# schematic.net
KiCad netlist of a schematic drawn in Altium Designer
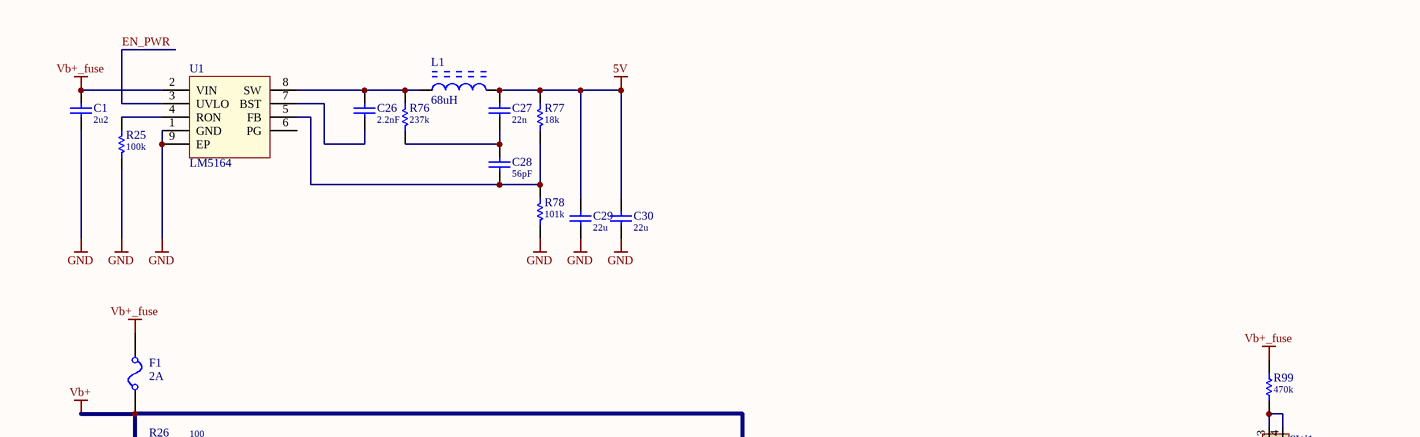
[diagram p0: schematic.SchDoc, top]
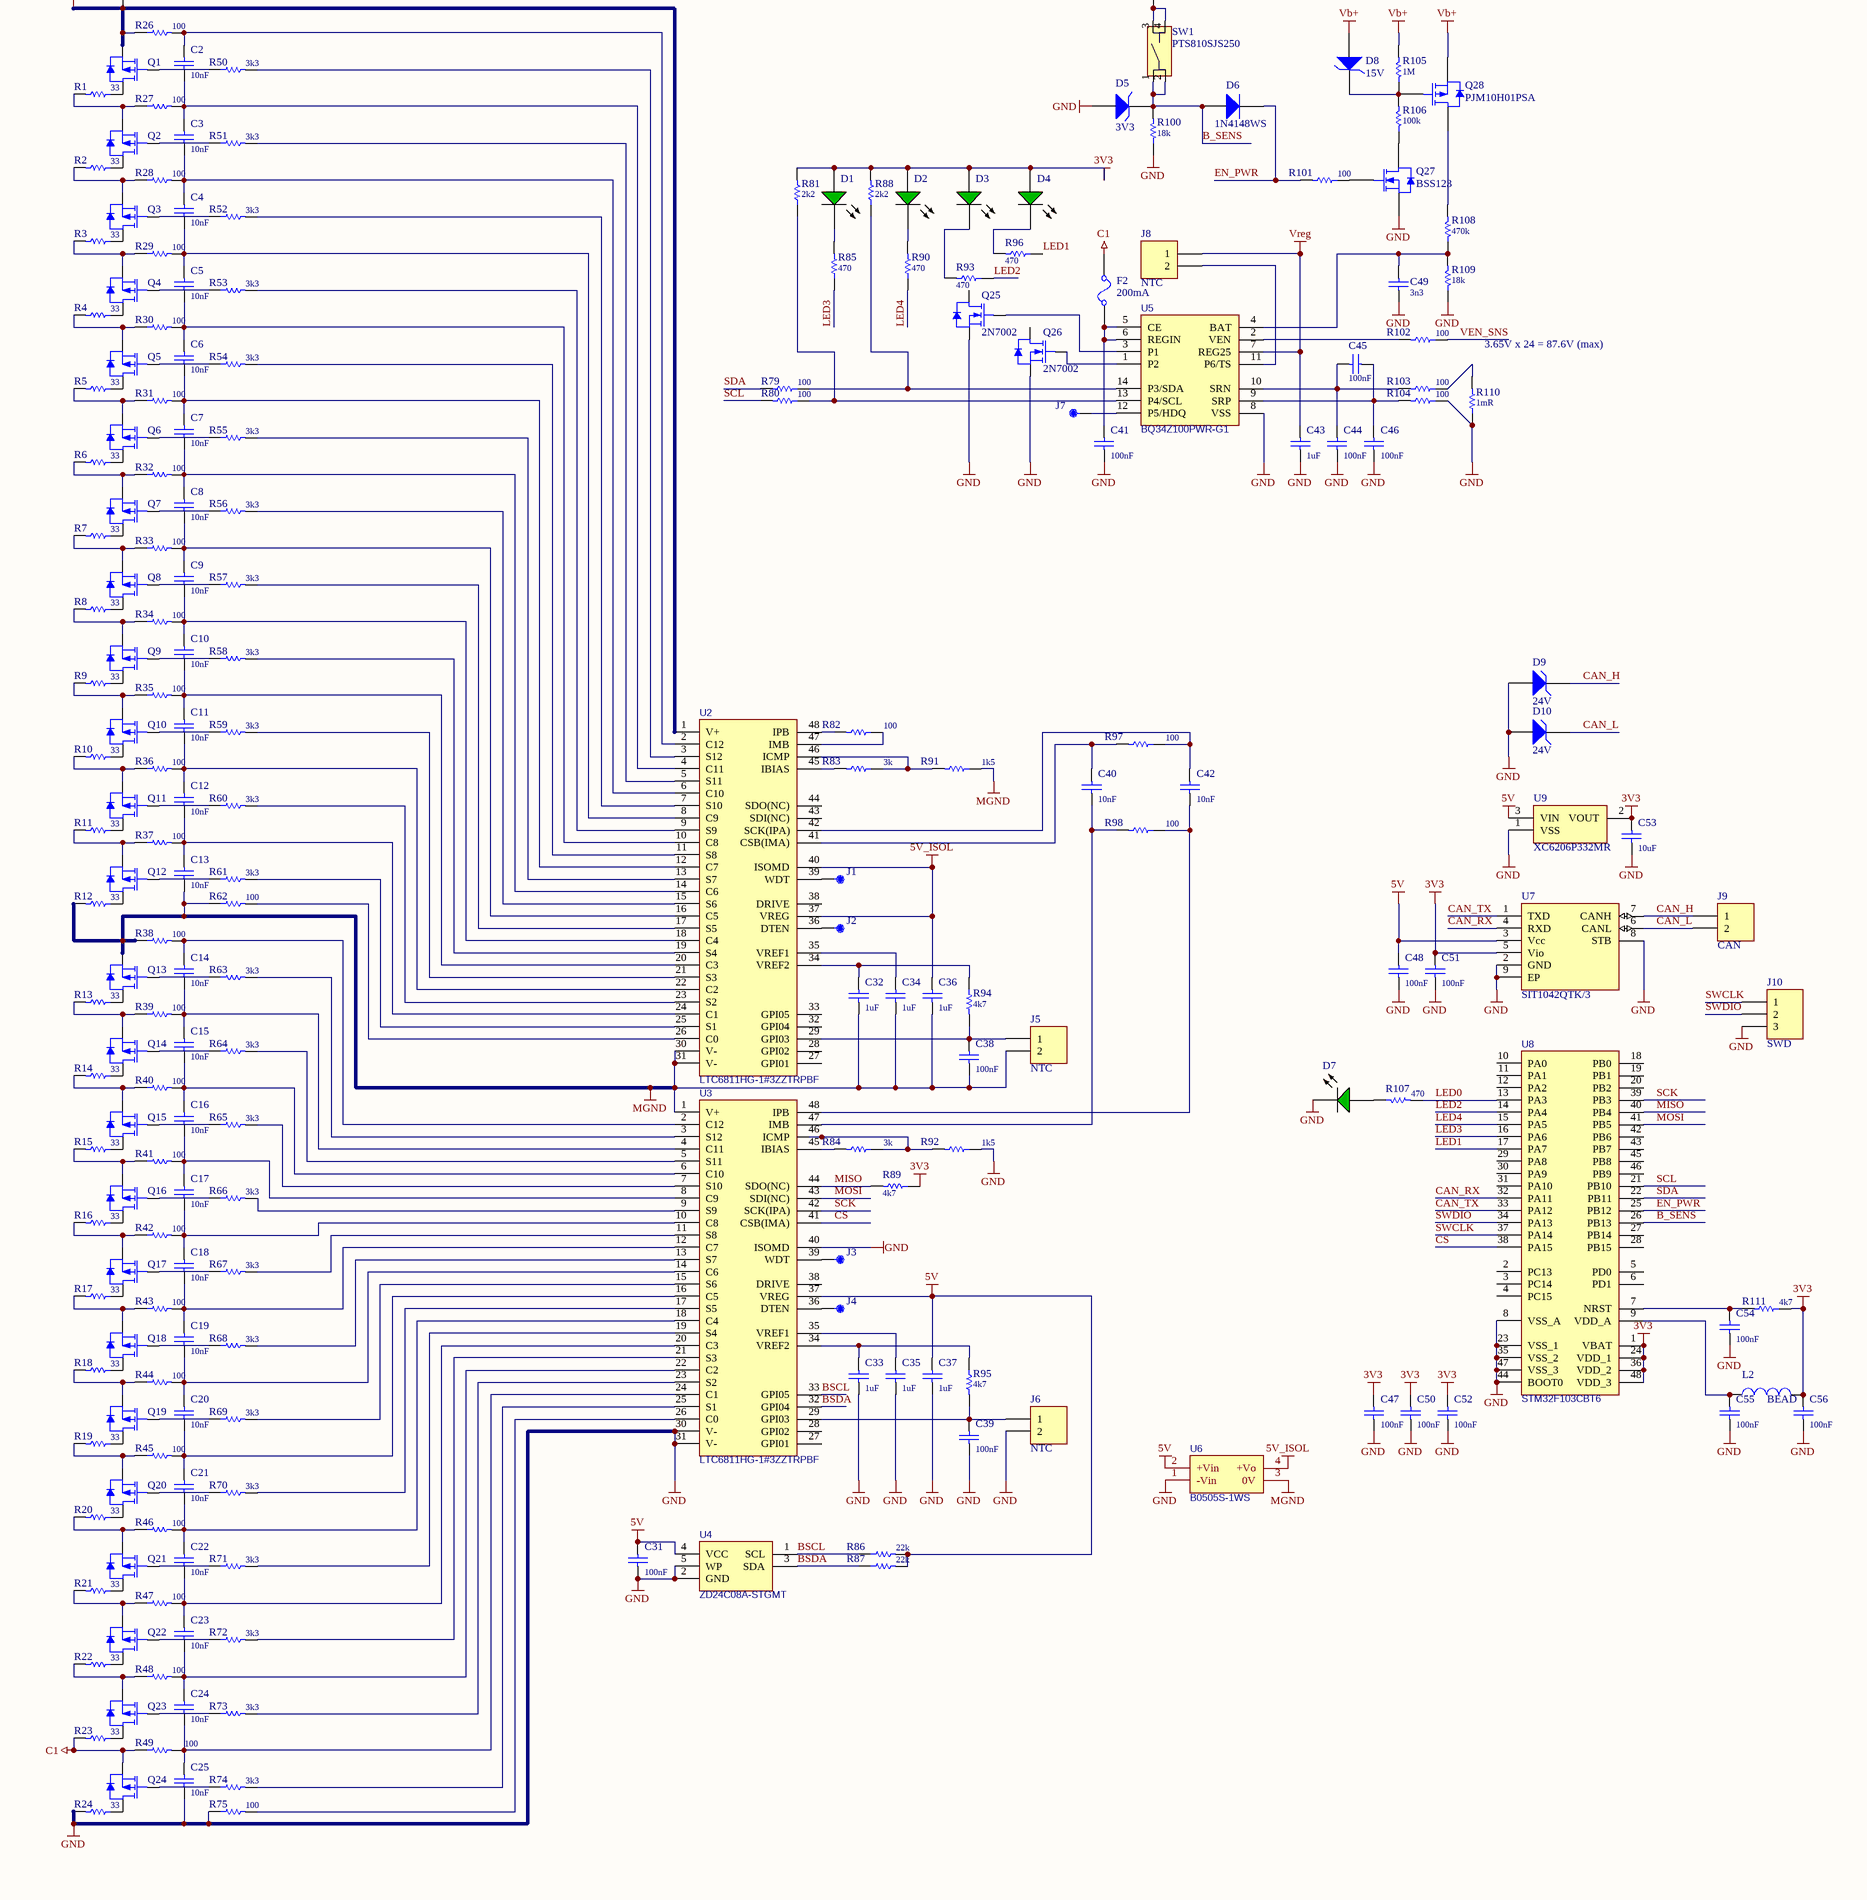
[diagram p1: schematic.SchDoc, bottom]

(export (version "E")
  (design (tool "Eeschema 10.0.6"))
  (components
    (comp (ref "C1")
      (value "2u2")
      (footprint "C1210")
      (description "2.2uF 100V 1210")
      (libsource (lib "Miscellaneous Devices") (part "CAP"))
    )
    (comp (ref "C2")
      (value "10nF")
      (footprint "C0603")
      (description "10nF 50V 0603")
      (libsource (lib "Miscellaneous Devices") (part "CAP"))
    )
    (comp (ref "C3")
      (value "10nF")
      (footprint "C0603")
      (description "10nF 50V 0603")
      (libsource (lib "Miscellaneous Devices") (part "CAP"))
    )
    (comp (ref "C4")
      (value "10nF")
      (footprint "C0603")
      (description "10nF 50V 0603")
      (libsource (lib "Miscellaneous Devices") (part "CAP"))
    )
    (comp (ref "C5")
      (value "10nF")
      (footprint "C0603")
      (description "10nF 50V 0603")
      (libsource (lib "Miscellaneous Devices") (part "CAP"))
    )
    (comp (ref "C6")
      (value "10nF")
      (footprint "C0603")
      (description "10nF 50V 0603")
      (libsource (lib "Miscellaneous Devices") (part "CAP"))
    )
    (comp (ref "C7")
      (value "10nF")
      (footprint "C0603")
      (description "10nF 50V 0603")
      (libsource (lib "Miscellaneous Devices") (part "CAP"))
    )
    (comp (ref "C8")
      (value "10nF")
      (footprint "C0603")
      (description "10nF 50V 0603")
      (libsource (lib "Miscellaneous Devices") (part "CAP"))
    )
    (comp (ref "C9")
      (value "10nF")
      (footprint "C0603")
      (description "10nF 50V 0603")
      (libsource (lib "Miscellaneous Devices") (part "CAP"))
    )
    (comp (ref "C10")
      (value "10nF")
      (footprint "C0603")
      (description "10nF 50V 0603")
      (libsource (lib "Miscellaneous Devices") (part "CAP"))
    )
    (comp (ref "C11")
      (value "10nF")
      (footprint "C0603")
      (description "10nF 50V 0603")
      (libsource (lib "Miscellaneous Devices") (part "CAP"))
    )
    (comp (ref "C12")
      (value "10nF")
      (footprint "C0603")
      (description "10nF 50V 0603")
      (libsource (lib "Miscellaneous Devices") (part "CAP"))
    )
    (comp (ref "C13")
      (value "10nF")
      (footprint "C0603")
      (description "10nF 50V 0603")
      (libsource (lib "Miscellaneous Devices") (part "CAP"))
    )
    (comp (ref "C14")
      (value "10nF")
      (footprint "C0603")
      (description "10nF 50V 0603")
      (libsource (lib "Miscellaneous Devices") (part "CAP"))
    )
    (comp (ref "C15")
      (value "10nF")
      (footprint "C0603")
      (description "10nF 50V 0603")
      (libsource (lib "Miscellaneous Devices") (part "CAP"))
    )
    (comp (ref "C16")
      (value "10nF")
      (footprint "C0603")
      (description "10nF 50V 0603")
      (libsource (lib "Miscellaneous Devices") (part "CAP"))
    )
    (comp (ref "C17")
      (value "10nF")
      (footprint "C0603")
      (description "10nF 50V 0603")
      (libsource (lib "Miscellaneous Devices") (part "CAP"))
    )
    (comp (ref "C18")
      (value "10nF")
      (footprint "C0603")
      (description "10nF 50V 0603")
      (libsource (lib "Miscellaneous Devices") (part "CAP"))
    )
    (comp (ref "C19")
      (value "10nF")
      (footprint "C0603")
      (description "10nF 50V 0603")
      (libsource (lib "Miscellaneous Devices") (part "CAP"))
    )
    (comp (ref "C20")
      (value "10nF")
      (footprint "C0603")
      (description "10nF 50V 0603")
      (libsource (lib "Miscellaneous Devices") (part "CAP"))
    )
    (comp (ref "C21")
      (value "10nF")
      (footprint "C0603")
      (description "10nF 50V 0603")
      (libsource (lib "Miscellaneous Devices") (part "CAP"))
    )
    (comp (ref "C22")
      (value "10nF")
      (footprint "C0603")
      (description "10nF 50V 0603")
      (libsource (lib "Miscellaneous Devices") (part "CAP"))
    )
    (comp (ref "C23")
      (value "10nF")
      (footprint "C0603")
      (description "10nF 50V 0603")
      (libsource (lib "Miscellaneous Devices") (part "CAP"))
    )
    (comp (ref "C24")
      (value "10nF")
      (footprint "C0603")
      (description "10nF 50V 0603")
      (libsource (lib "Miscellaneous Devices") (part "CAP"))
    )
    (comp (ref "C25")
      (value "10nF")
      (footprint "C0603")
      (description "10nF 50V 0603")
      (libsource (lib "Miscellaneous Devices") (part "CAP"))
    )
    (comp (ref "C26")
      (value "2.2nF")
      (footprint "C0603")
      (description "2.2nF 50V 0603")
      (libsource (lib "Miscellaneous Devices") (part "CAP"))
    )
    (comp (ref "C27")
      (value "22n")
      (footprint "C0603")
      (description "2.2nF 0603")
      (libsource (lib "Miscellaneous Devices") (part "CAP"))
    )
    (comp (ref "C28")
      (value "56pF")
      (footprint "C0603")
      (description "56pF 0603")
      (libsource (lib "Miscellaneous Devices") (part "CAP"))
    )
    (comp (ref "C29")
      (value "22u")
      (footprint "C1210")
      (description "22u 35V 1210")
      (libsource (lib "Miscellaneous Devices") (part "CAP"))
    )
    (comp (ref "C30")
      (value "22u")
      (footprint "C1210")
      (description "22u 35V 1210")
      (libsource (lib "Miscellaneous Devices") (part "CAP"))
    )
    (comp (ref "C31")
      (value "100nF")
      (footprint "C0402")
      (description "100nF 50V 0402")
      (libsource (lib "Miscellaneous Devices") (part "CAP"))
    )
    (comp (ref "C32")
      (value "1uF")
      (footprint "C0603")
      (description "1uF 0603")
      (libsource (lib "Miscellaneous Devices") (part "CAP"))
    )
    (comp (ref "C33")
      (value "1uF")
      (footprint "C0603")
      (description "1uF 0603")
      (libsource (lib "Miscellaneous Devices") (part "CAP"))
    )
    (comp (ref "C34")
      (value "1uF")
      (footprint "C0603")
      (description "1uF 0603")
      (libsource (lib "Miscellaneous Devices") (part "CAP"))
    )
    (comp (ref "C35")
      (value "1uF")
      (footprint "C0603")
      (description "1uF 0603")
      (libsource (lib "Miscellaneous Devices") (part "CAP"))
    )
    (comp (ref "C36")
      (value "1uF")
      (footprint "C0603")
      (description "1uF 0603")
      (libsource (lib "Miscellaneous Devices") (part "CAP"))
    )
    (comp (ref "C37")
      (value "1uF")
      (footprint "C0603")
      (description "1uF 0603")
      (libsource (lib "Miscellaneous Devices") (part "CAP"))
    )
    (comp (ref "C38")
      (value "100nF")
      (footprint "C0402")
      (description "100nF 50V 0402")
      (libsource (lib "Miscellaneous Devices") (part "CAP"))
    )
    (comp (ref "C39")
      (value "100nF")
      (footprint "C0402")
      (description "100nF 50V 0402")
      (libsource (lib "Miscellaneous Devices") (part "CAP"))
    )
    (comp (ref "C40")
      (value "10nF")
      (footprint "C0603")
      (description "10nF 50V 0402")
      (libsource (lib "Miscellaneous Devices") (part "CAP"))
    )
    (comp (ref "C41")
      (value "100nF")
      (footprint "C0603")
      (description "100nF 50V 0603")
      (libsource (lib "Miscellaneous Devices") (part "CAP"))
    )
    (comp (ref "C42")
      (value "10nF")
      (footprint "C0603")
      (description "10nF 50V 0402")
      (libsource (lib "Miscellaneous Devices") (part "CAP"))
    )
    (comp (ref "C43")
      (value "1uF")
      (footprint "C0603")
      (description "1uF 0603")
      (libsource (lib "Miscellaneous Devices") (part "CAP"))
    )
    (comp (ref "C44")
      (value "100nF")
      (footprint "C0603")
      (description "100nF 50V 0603")
      (libsource (lib "Miscellaneous Devices") (part "CAP"))
    )
    (comp (ref "C45")
      (value "100nF")
      (footprint "C0603")
      (description "100nF 50V 0603")
      (libsource (lib "Miscellaneous Devices") (part "CAP"))
    )
    (comp (ref "C46")
      (value "100nF")
      (footprint "C0603")
      (description "100nF 50V 0603")
      (libsource (lib "Miscellaneous Devices") (part "CAP"))
    )
    (comp (ref "C47")
      (value "100nF")
      (footprint "C0402")
      (description "100nF 50V 0402")
      (libsource (lib "Miscellaneous Devices") (part "CAP"))
    )
    (comp (ref "C48")
      (value "100nF")
      (footprint "C0402")
      (description "100nF 50V 0402")
      (libsource (lib "Miscellaneous Devices") (part "CAP"))
    )
    (comp (ref "C49")
      (value "3n3")
      (footprint "C0603")
      (description "3n3 100V 0603")
      (libsource (lib "Miscellaneous Devices") (part "CAP"))
    )
    (comp (ref "C50")
      (value "100nF")
      (footprint "C0402")
      (description "100nF 50V 0402")
      (libsource (lib "Miscellaneous Devices") (part "CAP"))
    )
    (comp (ref "C51")
      (value "100nF")
      (footprint "C0402")
      (description "100nF 50V 0402")
      (libsource (lib "Miscellaneous Devices") (part "CAP"))
    )
    (comp (ref "C52")
      (value "100nF")
      (footprint "C0402")
      (description "100nF 50V 0402")
      (libsource (lib "Miscellaneous Devices") (part "CAP"))
    )
    (comp (ref "C53")
      (value "10uF")
      (footprint "C1206")
      (description "10uf 50V 1206")
      (libsource (lib "Miscellaneous Devices") (part "CAP"))
    )
    (comp (ref "C54")
      (value "100nF")
      (footprint "C0402")
      (description "100nF 50V 0402")
      (libsource (lib "Miscellaneous Devices") (part "CAP"))
    )
    (comp (ref "C55")
      (value "100nF")
      (footprint "C0402")
      (description "100nF 50V 0402")
      (libsource (lib "Miscellaneous Devices") (part "CAP"))
    )
    (comp (ref "C56")
      (value "100nF")
      (footprint "C0402")
      (description "100nF 50V 0402")
      (libsource (lib "Miscellaneous Devices") (part "CAP"))
    )
    (comp (ref "D1")
      (value "GRN")
      (footprint "LED-0603-GRN")
      (description "LED 0603 GRN")
      (libsource (lib "Miscellaneous Devices") (part "LED-0603-GREEN"))
    )
    (comp (ref "D2")
      (value "GRN")
      (footprint "LED-0603-GRN")
      (description "LED 0603 GRN")
      (libsource (lib "Miscellaneous Devices") (part "LED-0603-GREEN"))
    )
    (comp (ref "D3")
      (value "GRN")
      (footprint "LED-0603-GRN")
      (description "LED 0603 GRN")
      (libsource (lib "Miscellaneous Devices") (part "LED-0603-GREEN"))
    )
    (comp (ref "D4")
      (value "GRN")
      (footprint "LED-0603-GRN")
      (description "LED 0603 GRN")
      (libsource (lib "Miscellaneous Devices") (part "LED-0603-GREEN"))
    )
    (comp (ref "D5")
      (value "3V3")
      (footprint "SOD-323")
      (libsource (lib "Miscellaneous Devices") (part "NCP51460SN33T1G"))
    )
    (comp (ref "D6")
      (value "1N4148WS")
      (footprint "SOD-323")
      (libsource (lib "Miscellaneous Devices") (part "US1M-13-F"))
    )
    (comp (ref "D7")
      (value "GRN")
      (footprint "LED-0603-GRN")
      (description "LED 0603 GRN")
      (libsource (lib "Miscellaneous Devices") (part "LED-0603-GREEN"))
    )
    (comp (ref "D8")
      (value "15V")
      (footprint "SOD-323")
      (description "BZT52C15S")
      (libsource (lib "") (part "NCP51460SN33T1G_1"))
    )
    (comp (ref "D9")
      (value "24V")
      (footprint "SOD-123FL")
      (description "P6SMB24A")
      (libsource (lib "Miscellaneous Devices") (part "SMCJ54A"))
    )
    (comp (ref "D10")
      (value "24V")
      (footprint "SOD-123FL")
      (description "P6SMB24A")
      (libsource (lib "Miscellaneous Devices") (part "SMCJ54A"))
    )
    (comp (ref "F1") (value "2A") (footprint "FUSE_2A_600V") (libsource (lib "Schlib1") (part "Component_1")))
    (comp (ref "F2") (value "200mA") (footprint "FUSE-1206") (libsource (lib "Schlib1") (part "Component_1")))
    (comp (ref "J1")
      (value "~")
      (footprint "TP30_SMD")
      (libsource (lib "Miscellaneous Connectors") (part "TP_Dup1"))
    )
    (comp (ref "J2")
      (value "~")
      (footprint "TP30_SMD")
      (libsource (lib "Miscellaneous Connectors") (part "TP_Dup1"))
    )
    (comp (ref "J3")
      (value "~")
      (footprint "TP30_SMD")
      (libsource (lib "Miscellaneous Connectors") (part "TP_Dup1"))
    )
    (comp (ref "J4")
      (value "~")
      (footprint "TP30_SMD")
      (libsource (lib "Miscellaneous Connectors") (part "TP_Dup1"))
    )
    (comp (ref "J5") (value "NTC") (footprint "HDR-1X2") (libsource (lib "Schlib1") (part "Header 2")))
    (comp (ref "J6") (value "NTC") (footprint "HDR-1X2") (libsource (lib "Schlib1") (part "Header 2")))
    (comp (ref "J7")
      (value "~")
      (footprint "TP30_SMD")
      (libsource (lib "Miscellaneous Connectors") (part "TP_Dup1"))
    )
    (comp (ref "J8") (value "NTC") (footprint "HDR-1X2") (libsource (lib "") (part "Header 2_1")))
    (comp (ref "J9") (value "CAN") (footprint "HDR-1X2") (libsource (lib "Schlib1") (part "Header 2")))
    (comp (ref "J10")
      (value "SWD")
      (footprint "HDR-1X3")
      (libsource (lib "Miscellaneous Devices") (part "Header 3"))
    )
    (comp (ref "L1")
      (value "68uH")
      (footprint "L0605-POWER")
      (description "PSPMAA0605H-680M-IGF")
      (libsource (lib "Miscellaneous Devices") (part "SRN3015-100M"))
    )
    (comp (ref "L2")
      (value "BEAD")
      (footprint "L0402")
      (description "BEAD 0402")
      (libsource (lib "Miscellaneous Devices") (part "BLM18AG601SN1D"))
    )
    (comp (ref "Q1")
      (value "BSS308PE-VB")
      (footprint "SOT-23")
      (libsource (lib "Miscellaneous Devices") (part "2N7002"))
    )
    (comp (ref "Q2")
      (value "BSS308PE-VB")
      (footprint "SOT-23")
      (libsource (lib "Miscellaneous Devices") (part "2N7002"))
    )
    (comp (ref "Q3")
      (value "BSS308PE-VB")
      (footprint "SOT-23")
      (libsource (lib "Miscellaneous Devices") (part "2N7002"))
    )
    (comp (ref "Q4")
      (value "BSS308PE-VB")
      (footprint "SOT-23")
      (libsource (lib "Miscellaneous Devices") (part "2N7002"))
    )
    (comp (ref "Q5")
      (value "BSS308PE-VB")
      (footprint "SOT-23")
      (libsource (lib "Miscellaneous Devices") (part "2N7002"))
    )
    (comp (ref "Q6")
      (value "BSS308PE-VB")
      (footprint "SOT-23")
      (libsource (lib "Miscellaneous Devices") (part "2N7002"))
    )
    (comp (ref "Q7")
      (value "BSS308PE-VB")
      (footprint "SOT-23")
      (libsource (lib "Miscellaneous Devices") (part "2N7002"))
    )
    (comp (ref "Q8")
      (value "BSS308PE-VB")
      (footprint "SOT-23")
      (libsource (lib "Miscellaneous Devices") (part "2N7002"))
    )
    (comp (ref "Q9")
      (value "BSS308PE-VB")
      (footprint "SOT-23")
      (libsource (lib "Miscellaneous Devices") (part "2N7002"))
    )
    (comp (ref "Q10")
      (value "BSS308PE-VB")
      (footprint "SOT-23")
      (libsource (lib "Miscellaneous Devices") (part "2N7002"))
    )
    (comp (ref "Q11")
      (value "BSS308PE-VB")
      (footprint "SOT-23")
      (libsource (lib "Miscellaneous Devices") (part "2N7002"))
    )
    (comp (ref "Q12")
      (value "BSS308PE-VB")
      (footprint "SOT-23")
      (libsource (lib "Miscellaneous Devices") (part "2N7002"))
    )
    (comp (ref "Q13")
      (value "BSS308PE-VB")
      (footprint "SOT-23")
      (libsource (lib "Miscellaneous Devices") (part "2N7002"))
    )
    (comp (ref "Q14")
      (value "BSS308PE-VB")
      (footprint "SOT-23")
      (libsource (lib "Miscellaneous Devices") (part "2N7002"))
    )
    (comp (ref "Q15")
      (value "BSS308PE-VB")
      (footprint "SOT-23")
      (libsource (lib "Miscellaneous Devices") (part "2N7002"))
    )
    (comp (ref "Q16")
      (value "BSS308PE-VB")
      (footprint "SOT-23")
      (libsource (lib "Miscellaneous Devices") (part "2N7002"))
    )
    (comp (ref "Q17")
      (value "BSS308PE-VB")
      (footprint "SOT-23")
      (libsource (lib "Miscellaneous Devices") (part "2N7002"))
    )
    (comp (ref "Q18")
      (value "BSS308PE-VB")
      (footprint "SOT-23")
      (libsource (lib "Miscellaneous Devices") (part "2N7002"))
    )
    (comp (ref "Q19")
      (value "BSS308PE-VB")
      (footprint "SOT-23")
      (libsource (lib "Miscellaneous Devices") (part "2N7002"))
    )
    (comp (ref "Q20")
      (value "BSS308PE-VB")
      (footprint "SOT-23")
      (libsource (lib "Miscellaneous Devices") (part "2N7002"))
    )
    (comp (ref "Q21")
      (value "BSS308PE-VB")
      (footprint "SOT-23")
      (libsource (lib "Miscellaneous Devices") (part "2N7002"))
    )
    (comp (ref "Q22")
      (value "BSS308PE-VB")
      (footprint "SOT-23")
      (libsource (lib "Miscellaneous Devices") (part "2N7002"))
    )
    (comp (ref "Q23")
      (value "BSS308PE-VB")
      (footprint "SOT-23")
      (libsource (lib "Miscellaneous Devices") (part "2N7002"))
    )
    (comp (ref "Q24")
      (value "BSS308PE-VB")
      (footprint "SOT-23")
      (libsource (lib "Miscellaneous Devices") (part "2N7002"))
    )
    (comp (ref "Q25") (value "2N7002") (footprint "SOT-23") (libsource (lib "") (part "2N7002_2")))
    (comp (ref "Q26") (value "2N7002") (footprint "SOT-23") (libsource (lib "") (part "2N7002_2")))
    (comp (ref "Q27") (value "BSS123") (footprint "SOT-23") (libsource (lib "") (part "2N7002_1")))
    (comp (ref "Q28") (value "PJM10H01PSA") (footprint "SOT-23") (libsource (lib "Schlib1") (part "2N7002")))
    (comp (ref "R1")
      (value "33")
      (footprint "R2512")
      (description "33R 2512")
      (libsource (lib "Miscellaneous Devices") (part "RES"))
    )
    (comp (ref "R2")
      (value "33")
      (footprint "R2512")
      (description "33R 2512")
      (libsource (lib "Miscellaneous Devices") (part "RES"))
    )
    (comp (ref "R3")
      (value "33")
      (footprint "R2512")
      (description "33R 2512")
      (libsource (lib "Miscellaneous Devices") (part "RES"))
    )
    (comp (ref "R4")
      (value "33")
      (footprint "R2512")
      (description "33R 2512")
      (libsource (lib "Miscellaneous Devices") (part "RES"))
    )
    (comp (ref "R5")
      (value "33")
      (footprint "R2512")
      (description "33R 2512")
      (libsource (lib "Miscellaneous Devices") (part "RES"))
    )
    (comp (ref "R6")
      (value "33")
      (footprint "R2512")
      (description "33R 2512")
      (libsource (lib "Miscellaneous Devices") (part "RES"))
    )
    (comp (ref "R7")
      (value "33")
      (footprint "R2512")
      (description "33R 2512")
      (libsource (lib "Miscellaneous Devices") (part "RES"))
    )
    (comp (ref "R8")
      (value "33")
      (footprint "R2512")
      (description "33R 2512")
      (libsource (lib "Miscellaneous Devices") (part "RES"))
    )
    (comp (ref "R9")
      (value "33")
      (footprint "R2512")
      (description "33R 2512")
      (libsource (lib "Miscellaneous Devices") (part "RES"))
    )
    (comp (ref "R10")
      (value "33")
      (footprint "R2512")
      (description "33R 2512")
      (libsource (lib "Miscellaneous Devices") (part "RES"))
    )
    (comp (ref "R11")
      (value "33")
      (footprint "R2512")
      (description "33R 2512")
      (libsource (lib "Miscellaneous Devices") (part "RES"))
    )
    (comp (ref "R12")
      (value "33")
      (footprint "R2512")
      (description "33R 2512")
      (libsource (lib "Miscellaneous Devices") (part "RES"))
    )
    (comp (ref "R13")
      (value "33")
      (footprint "R2512")
      (description "33R 2512")
      (libsource (lib "Miscellaneous Devices") (part "RES"))
    )
    (comp (ref "R14")
      (value "33")
      (footprint "R2512")
      (description "33R 2512")
      (libsource (lib "Miscellaneous Devices") (part "RES"))
    )
    (comp (ref "R15")
      (value "33")
      (footprint "R2512")
      (description "33R 2512")
      (libsource (lib "Miscellaneous Devices") (part "RES"))
    )
    (comp (ref "R16")
      (value "33")
      (footprint "R2512")
      (description "33R 2512")
      (libsource (lib "Miscellaneous Devices") (part "RES"))
    )
    (comp (ref "R17")
      (value "33")
      (footprint "R2512")
      (description "33R 2512")
      (libsource (lib "Miscellaneous Devices") (part "RES"))
    )
    (comp (ref "R18")
      (value "33")
      (footprint "R2512")
      (description "33R 2512")
      (libsource (lib "Miscellaneous Devices") (part "RES"))
    )
    (comp (ref "R19")
      (value "33")
      (footprint "R2512")
      (description "33R 2512")
      (libsource (lib "Miscellaneous Devices") (part "RES"))
    )
    (comp (ref "R20")
      (value "33")
      (footprint "R2512")
      (description "33R 2512")
      (libsource (lib "Miscellaneous Devices") (part "RES"))
    )
    (comp (ref "R21")
      (value "33")
      (footprint "R2512")
      (description "33R 2512")
      (libsource (lib "Miscellaneous Devices") (part "RES"))
    )
    (comp (ref "R22")
      (value "33")
      (footprint "R2512")
      (description "33R 2512")
      (libsource (lib "Miscellaneous Devices") (part "RES"))
    )
    (comp (ref "R23")
      (value "33")
      (footprint "R2512")
      (description "33R 2512")
      (libsource (lib "Miscellaneous Devices") (part "RES"))
    )
    (comp (ref "R24")
      (value "33")
      (footprint "R2512")
      (description "33R 2512")
      (libsource (lib "Miscellaneous Devices") (part "RES"))
    )
    (comp (ref "R25")
      (value "100k")
      (footprint "R0603")
      (description "100k 0603")
      (libsource (lib "Miscellaneous Devices") (part "RES"))
    )
    (comp (ref "R26")
      (value "100")
      (footprint "R0603")
      (description "100R 0603")
      (libsource (lib "Miscellaneous Devices") (part "RES"))
    )
    (comp (ref "R27")
      (value "100")
      (footprint "R0603")
      (description "100R 0603")
      (libsource (lib "Miscellaneous Devices") (part "RES"))
    )
    (comp (ref "R28")
      (value "100")
      (footprint "R0603")
      (description "100R 0603")
      (libsource (lib "Miscellaneous Devices") (part "RES"))
    )
    (comp (ref "R29")
      (value "100")
      (footprint "R0603")
      (description "100R 0603")
      (libsource (lib "Miscellaneous Devices") (part "RES"))
    )
    (comp (ref "R30")
      (value "100")
      (footprint "R0603")
      (description "100R 0603")
      (libsource (lib "Miscellaneous Devices") (part "RES"))
    )
    (comp (ref "R31")
      (value "100")
      (footprint "R0603")
      (description "100R 0603")
      (libsource (lib "Miscellaneous Devices") (part "RES"))
    )
    (comp (ref "R32")
      (value "100")
      (footprint "R0603")
      (description "100R 0603")
      (libsource (lib "Miscellaneous Devices") (part "RES"))
    )
    (comp (ref "R33")
      (value "100")
      (footprint "R0603")
      (description "100R 0603")
      (libsource (lib "Miscellaneous Devices") (part "RES"))
    )
    (comp (ref "R34")
      (value "100")
      (footprint "R0603")
      (description "100R 0603")
      (libsource (lib "Miscellaneous Devices") (part "RES"))
    )
    (comp (ref "R35")
      (value "100")
      (footprint "R0603")
      (description "100R 0603")
      (libsource (lib "Miscellaneous Devices") (part "RES"))
    )
    (comp (ref "R36")
      (value "100")
      (footprint "R0603")
      (description "100R 0603")
      (libsource (lib "Miscellaneous Devices") (part "RES"))
    )
    (comp (ref "R37")
      (value "100")
      (footprint "R0603")
      (description "100R 0603")
      (libsource (lib "Miscellaneous Devices") (part "RES"))
    )
    (comp (ref "R38")
      (value "100")
      (footprint "R0603")
      (description "100R 0603")
      (libsource (lib "Miscellaneous Devices") (part "RES"))
    )
    (comp (ref "R39")
      (value "100")
      (footprint "R0603")
      (description "100R 0603")
      (libsource (lib "Miscellaneous Devices") (part "RES"))
    )
    (comp (ref "R40")
      (value "100")
      (footprint "R0603")
      (description "100R 0603")
      (libsource (lib "Miscellaneous Devices") (part "RES"))
    )
    (comp (ref "R41")
      (value "100")
      (footprint "R0603")
      (description "100R 0603")
      (libsource (lib "Miscellaneous Devices") (part "RES"))
    )
    (comp (ref "R42")
      (value "100")
      (footprint "R0603")
      (description "100R 0603")
      (libsource (lib "Miscellaneous Devices") (part "RES"))
    )
    (comp (ref "R43")
      (value "100")
      (footprint "R0603")
      (description "100R 0603")
      (libsource (lib "Miscellaneous Devices") (part "RES"))
    )
    (comp (ref "R44")
      (value "100")
      (footprint "R0603")
      (description "100R 0603")
      (libsource (lib "Miscellaneous Devices") (part "RES"))
    )
    (comp (ref "R45")
      (value "100")
      (footprint "R0603")
      (description "100R 0603")
      (libsource (lib "Miscellaneous Devices") (part "RES"))
    )
    (comp (ref "R46")
      (value "100")
      (footprint "R0603")
      (description "100R 0603")
      (libsource (lib "Miscellaneous Devices") (part "RES"))
    )
    (comp (ref "R47")
      (value "100")
      (footprint "R0603")
      (description "100R 0603")
      (libsource (lib "Miscellaneous Devices") (part "RES"))
    )
    (comp (ref "R48")
      (value "100")
      (footprint "R0603")
      (description "100R 0603")
      (libsource (lib "Miscellaneous Devices") (part "RES"))
    )
    (comp (ref "R49")
      (value "100")
      (footprint "R0603")
      (description "100R 0603")
      (libsource (lib "Miscellaneous Devices") (part "RES"))
    )
    (comp (ref "R50")
      (value "3k3")
      (footprint "R0603")
      (description "3k3 0603")
      (libsource (lib "Miscellaneous Devices") (part "RES"))
    )
    (comp (ref "R51")
      (value "3k3")
      (footprint "R0603")
      (description "3k3 0603")
      (libsource (lib "Miscellaneous Devices") (part "RES"))
    )
    (comp (ref "R52")
      (value "3k3")
      (footprint "R0603")
      (description "3k3 0603")
      (libsource (lib "Miscellaneous Devices") (part "RES"))
    )
    (comp (ref "R53")
      (value "3k3")
      (footprint "R0603")
      (description "3k3 0603")
      (libsource (lib "Miscellaneous Devices") (part "RES"))
    )
    (comp (ref "R54")
      (value "3k3")
      (footprint "R0603")
      (description "3k3 0603")
      (libsource (lib "Miscellaneous Devices") (part "RES"))
    )
    (comp (ref "R55")
      (value "3k3")
      (footprint "R0603")
      (description "3k3 0603")
      (libsource (lib "Miscellaneous Devices") (part "RES"))
    )
    (comp (ref "R56")
      (value "3k3")
      (footprint "R0603")
      (description "3k3 0603")
      (libsource (lib "Miscellaneous Devices") (part "RES"))
    )
    (comp (ref "R57")
      (value "3k3")
      (footprint "R0603")
      (description "3k3 0603")
      (libsource (lib "Miscellaneous Devices") (part "RES"))
    )
    (comp (ref "R58")
      (value "3k3")
      (footprint "R0603")
      (description "3k3 0603")
      (libsource (lib "Miscellaneous Devices") (part "RES"))
    )
    (comp (ref "R59")
      (value "3k3")
      (footprint "R0603")
      (description "3k3 0603")
      (libsource (lib "Miscellaneous Devices") (part "RES"))
    )
    (comp (ref "R60")
      (value "3k3")
      (footprint "R0603")
      (description "3k3 0603")
      (libsource (lib "Miscellaneous Devices") (part "RES"))
    )
    (comp (ref "R61")
      (value "3k3")
      (footprint "R0603")
      (description "3k3 0603")
      (libsource (lib "Miscellaneous Devices") (part "RES"))
    )
    (comp (ref "R62")
      (value "100")
      (footprint "R0603")
      (description "100R 0603")
      (libsource (lib "Miscellaneous Devices") (part "RES"))
    )
    (comp (ref "R63")
      (value "3k3")
      (footprint "R0603")
      (description "3k3 0603")
      (libsource (lib "Miscellaneous Devices") (part "RES"))
    )
    (comp (ref "R64")
      (value "3k3")
      (footprint "R0603")
      (description "3k3 0603")
      (libsource (lib "Miscellaneous Devices") (part "RES"))
    )
    (comp (ref "R65")
      (value "3k3")
      (footprint "R0603")
      (description "3k3 0603")
      (libsource (lib "Miscellaneous Devices") (part "RES"))
    )
    (comp (ref "R66")
      (value "3k3")
      (footprint "R0603")
      (description "3k3 0603")
      (libsource (lib "Miscellaneous Devices") (part "RES"))
    )
    (comp (ref "R67")
      (value "3k3")
      (footprint "R0603")
      (description "3k3 0603")
      (libsource (lib "Miscellaneous Devices") (part "RES"))
    )
    (comp (ref "R68")
      (value "3k3")
      (footprint "R0603")
      (description "3k3 0603")
      (libsource (lib "Miscellaneous Devices") (part "RES"))
    )
    (comp (ref "R69")
      (value "3k3")
      (footprint "R0603")
      (description "3k3 0603")
      (libsource (lib "Miscellaneous Devices") (part "RES"))
    )
    (comp (ref "R70")
      (value "3k3")
      (footprint "R0603")
      (description "3k3 0603")
      (libsource (lib "Miscellaneous Devices") (part "RES"))
    )
    (comp (ref "R71")
      (value "3k3")
      (footprint "R0603")
      (description "3k3 0603")
      (libsource (lib "Miscellaneous Devices") (part "RES"))
    )
    (comp (ref "R72")
      (value "3k3")
      (footprint "R0603")
      (description "3k3 0603")
      (libsource (lib "Miscellaneous Devices") (part "RES"))
    )
    (comp (ref "R73")
      (value "3k3")
      (footprint "R0603")
      (description "3k3 0603")
      (libsource (lib "Miscellaneous Devices") (part "RES"))
    )
    (comp (ref "R74")
      (value "3k3")
      (footprint "R0603")
      (description "3k3 0603")
      (libsource (lib "Miscellaneous Devices") (part "RES"))
    )
    (comp (ref "R75")
      (value "100")
      (footprint "R0603")
      (description "100R 0603")
      (libsource (lib "Miscellaneous Devices") (part "RES"))
    )
    (comp (ref "R76")
      (value "237k")
      (footprint "R0603")
      (description "237k 0603")
      (libsource (lib "Miscellaneous Devices") (part "RES"))
    )
    (comp (ref "R77")
      (value "18k")
      (footprint "R0603")
      (description "18k 1% 0603")
      (libsource (lib "Miscellaneous Devices") (part "RES"))
    )
    (comp (ref "R78")
      (value "101k")
      (footprint "R0603")
      (description "101k 0603")
      (libsource (lib "Miscellaneous Devices") (part "RES"))
    )
    (comp (ref "R79")
      (value "100")
      (footprint "R0603")
      (description "100R 0603")
      (libsource (lib "Miscellaneous Devices") (part "RES"))
    )
    (comp (ref "R80")
      (value "100")
      (footprint "R0603")
      (description "100R 0603")
      (libsource (lib "Miscellaneous Devices") (part "RES"))
    )
    (comp (ref "R81")
      (value "2k2")
      (footprint "R0603")
      (description "2.2k 0603")
      (libsource (lib "Miscellaneous Devices") (part "RES"))
    )
    (comp (ref "R82")
      (value "100")
      (footprint "R0603")
      (description "100R 0603")
      (libsource (lib "Miscellaneous Devices") (part "RES"))
    )
    (comp (ref "R83")
      (value "3k")
      (footprint "R0603")
      (description "3k 0603")
      (libsource (lib "Miscellaneous Devices") (part "RES"))
    )
    (comp (ref "R84")
      (value "3k")
      (footprint "R0603")
      (description "3k 0603")
      (libsource (lib "Miscellaneous Devices") (part "RES"))
    )
    (comp (ref "R85")
      (value "470")
      (footprint "R0603")
      (description "470R 0603")
      (libsource (lib "Miscellaneous Devices") (part "RES"))
    )
    (comp (ref "R86")
      (value "22k")
      (footprint "R0402")
      (description "22k 0402")
      (libsource (lib "Miscellaneous Devices") (part "RES"))
    )
    (comp (ref "R87")
      (value "22k")
      (footprint "R0402")
      (description "22k 0402")
      (libsource (lib "Miscellaneous Devices") (part "RES"))
    )
    (comp (ref "R88")
      (value "2k2")
      (footprint "R0603")
      (description "2.2k 0603")
      (libsource (lib "Miscellaneous Devices") (part "RES"))
    )
    (comp (ref "R89")
      (value "4k7")
      (footprint "R0402")
      (description "4.7k 0603")
      (libsource (lib "Miscellaneous Devices") (part "RES"))
    )
    (comp (ref "R90")
      (value "470")
      (footprint "R0603")
      (description "470R 0603")
      (libsource (lib "Miscellaneous Devices") (part "RES"))
    )
    (comp (ref "R91")
      (value "1k5")
      (footprint "R0603")
      (description "1.5k 0603")
      (libsource (lib "Miscellaneous Devices") (part "RES"))
    )
    (comp (ref "R92")
      (value "1k5")
      (footprint "R0603")
      (description "1.5k 0603")
      (libsource (lib "Miscellaneous Devices") (part "RES"))
    )
    (comp (ref "R93")
      (value "470")
      (footprint "R0603")
      (description "470R 0603")
      (libsource (lib "Miscellaneous Devices") (part "RES"))
    )
    (comp (ref "R94")
      (value "4k7")
      (footprint "R0603")
      (description "4.7k 0603")
      (libsource (lib "Miscellaneous Devices") (part "RES"))
    )
    (comp (ref "R95")
      (value "4k7")
      (footprint "R0603")
      (description "4.7k 0603")
      (libsource (lib "Miscellaneous Devices") (part "RES"))
    )
    (comp (ref "R96")
      (value "470")
      (footprint "R0603")
      (description "470R 0603")
      (libsource (lib "Miscellaneous Devices") (part "RES"))
    )
    (comp (ref "R97")
      (value "100")
      (footprint "R0603")
      (description "100R 0603")
      (libsource (lib "Miscellaneous Devices") (part "RES"))
    )
    (comp (ref "R98")
      (value "100")
      (footprint "R0603")
      (description "100R 0603")
      (libsource (lib "Miscellaneous Devices") (part "RES"))
    )
    (comp (ref "R99")
      (value "470k")
      (footprint "R1206")
      (description "470k 1206")
      (libsource (lib "Miscellaneous Devices") (part "RES"))
    )
    (comp (ref "R100")
      (value "18k")
      (footprint "R0603")
      (description "18k 0603")
      (libsource (lib "Miscellaneous Devices") (part "RES"))
    )
    (comp (ref "R101")
      (value "100")
      (footprint "R0603")
      (description "100R 1% 0603")
      (libsource (lib "Miscellaneous Devices") (part "RES"))
    )
    (comp (ref "R102")
      (value "100")
      (footprint "R0603")
      (description "100R 0603")
      (libsource (lib "Miscellaneous Devices") (part "RES"))
    )
    (comp (ref "R103")
      (value "100")
      (footprint "R0603")
      (description "100R 0603")
      (libsource (lib "Miscellaneous Devices") (part "RES"))
    )
    (comp (ref "R104")
      (value "100")
      (footprint "R0603")
      (description "100R 0603")
      (libsource (lib "Miscellaneous Devices") (part "RES"))
    )
    (comp (ref "R105")
      (value "1M")
      (footprint "R1206")
      (description "1M 1206")
      (libsource (lib "Miscellaneous Devices") (part "RES"))
    )
    (comp (ref "R106")
      (value "100k")
      (footprint "R1206")
      (description "100k 1206")
      (libsource (lib "Miscellaneous Devices") (part "RES"))
    )
    (comp (ref "R107")
      (value "470")
      (footprint "R0603")
      (description "470 0603")
      (libsource (lib "Miscellaneous Devices") (part "RES"))
    )
    (comp (ref "R108")
      (value "470k")
      (footprint "R1206")
      (description "470k 1206")
      (libsource (lib "Miscellaneous Devices") (part "RES"))
    )
    (comp (ref "R109")
      (value "18k")
      (footprint "R0603")
      (description "18k 0603")
      (libsource (lib "Miscellaneous Devices") (part "RES"))
    )
    (comp (ref "R110")
      (value "1mR")
      (footprint "R5930_SHUNT")
      (description "HolRS5930-7W-1mR-1%")
      (libsource (lib "Miscellaneous Devices") (part "RES"))
    )
    (comp (ref "R111")
      (value "4k7")
      (footprint "R0402")
      (description "4k7 0402")
      (libsource (lib "Miscellaneous Devices") (part "RES"))
    )
    (comp (ref "SW1")
      (value "PTS810SJS250")
      (footprint "BTN_PTS810")
      (libsource (lib "Miscellaneous Devices") (part "Component_1"))
    )
    (comp (ref "U1") (value "LM5164") (footprint "PowerSOIC-8") (libsource (lib "Schlib2") (part "LM5164")))
    (comp (ref "U2")
      (value "LTC6811HG-1#3ZZTRPBF")
      (footprint "SSOP-48_L12.8-W5.3-P0.50-LS7.8-BL")
      (libsource (lib "Schlib1") (part "LTC6811HG-1#3ZZTRPBF"))
    )
    (comp (ref "U3")
      (value "LTC6811HG-1#3ZZTRPBF")
      (footprint "SSOP-48_L12.8-W5.3-P0.50-LS7.8-BL")
      (libsource (lib "Schlib1") (part "LTC6811HG-1#3ZZTRPBF"))
    )
    (comp (ref "U4")
      (value "ZD24C08A-STGMT")
      (footprint "SOT-23-5")
      (libsource (lib "Schlib1") (part "ZD24C08A-STGMT"))
    )
    (comp (ref "U5")
      (value "BQ34Z100PWR-G1")
      (footprint "TSSOP-14_L5.0-W4.4-P0.65-LS6.4-BL")
      (libsource (lib "Schlib1") (part "BQ34Z100PWR-G1"))
    )
    (comp (ref "U6")
      (value "B0505S-1WS")
      (footprint "B0505S-1WS")
      (libsource (lib "Schlib1") (part "B0505S-1WR3_C512048"))
    )
    (comp (ref "U7")
      (value "SIT1042QTK/3")
      (footprint "DFN8_3X3_P065")
      (description "IC INTERFACE CAN")
      (libsource (lib "Miscellaneous Devices") (part "LTC2875"))
    )
    (comp (ref "U8")
      (value "STM32F103CBT6")
      (footprint "LQFP-48")
      (libsource (lib "Schlib1") (part "STM32F103CBT6"))
    )
    (comp (ref "U9")
      (value "XC6206P332MR")
      (footprint "SOT-23")
      (libsource (lib "Schlib1") (part "Component_4_1"))
    )
  )
  (nets
    (net (code "1") (name "/BSCL") (class "Default")
      (node (ref "R86") (pin "1") (pinfunction "1_1") (pintype "passive"))
      (node (ref "U3") (pin "33") (pinfunction "GPI05_33") (pintype "passive"))
      (node (ref "U4") (pin "1") (pinfunction "SCL_1") (pintype "passive"))
    )
    (net (code "2") (name "/BSDA") (class "Default")
      (node (ref "R87") (pin "1") (pinfunction "1_1") (pintype "passive"))
      (node (ref "U3") (pin "32") (pinfunction "GPI04_32") (pintype "passive"))
      (node (ref "U4") (pin "3") (pinfunction "SDA_3") (pintype "passive"))
    )
    (net (code "3") (name "/B_SENS") (class "Default")
      (node (ref "D5") (pin "2") (pinfunction "-_2") (pintype "passive"))
      (node (ref "D6") (pin "1") (pinfunction "A_1") (pintype "passive"))
      (node (ref "R100") (pin "2") (pinfunction "2_2") (pintype "passive"))
      (node (ref "SW1") (pin "1") (pinfunction "1_1") (pintype "passive"))
      (node (ref "SW1") (pin "2") (pinfunction "2_2") (pintype "passive"))
      (node (ref "U8") (pin "26") (pinfunction "PB13_26") (pintype "passive"))
    )
    (net (code "4") (name "/CAN_H") (class "Default")
      (node (ref "D9") (pin "2") (pinfunction "K_2") (pintype "passive"))
      (node (ref "J9") (pin "1") (pinfunction "1_1") (pintype "passive"))
      (node (ref "U7") (pin "7") (pinfunction "CANH_7") (pintype "bidirectional"))
    )
    (net (code "5") (name "/CAN_L") (class "Default")
      (node (ref "D10") (pin "2") (pinfunction "K_2") (pintype "passive"))
      (node (ref "J9") (pin "2") (pinfunction "2_2") (pintype "passive"))
      (node (ref "U7") (pin "6") (pinfunction "CANL_6") (pintype "bidirectional"))
    )
    (net (code "6") (name "/CAN_RX") (class "Default")
      (node (ref "U7") (pin "4") (pinfunction "RXD_4") (pintype "passive"))
      (node (ref "U8") (pin "32") (pinfunction "PA11_32") (pintype "passive"))
    )
    (net (code "7") (name "/CAN_TX") (class "Default")
      (node (ref "U7") (pin "1") (pinfunction "TXD_1") (pintype "passive"))
      (node (ref "U8") (pin "33") (pinfunction "PA12_33") (pintype "passive"))
    )
    (net (code "8") (name "/CS") (class "Default")
      (node (ref "U3") (pin "41") (pinfunction "CSB(IMA)_41") (pintype "passive"))
      (node (ref "U8") (pin "38") (pinfunction "PA15_38") (pintype "passive"))
    )
    (net (code "9") (name "/EN_PWR") (class "Default")
      (node (ref "D6") (pin "2") (pinfunction "K_2") (pintype "passive"))
      (node (ref "R101") (pin "2") (pinfunction "2_2") (pintype "passive"))
      (node (ref "U1") (pin "3") (pinfunction "UVLO_3") (pintype "passive"))
      (node (ref "U8") (pin "25") (pinfunction "PB12_25") (pintype "passive"))
    )
    (net (code "10") (name "/LED0") (class "Default")
      (node (ref "R107") (pin "2") (pinfunction "2_2") (pintype "passive"))
      (node (ref "U8") (pin "13") (pinfunction "PA3_13") (pintype "passive"))
    )
    (net (code "11") (name "/LED1") (class "Default")
      (node (ref "R96") (pin "1") (pinfunction "1_1") (pintype "passive"))
      (node (ref "U8") (pin "17") (pinfunction "PA7_17") (pintype "passive"))
    )
    (net (code "12") (name "/LED2") (class "Default")
      (node (ref "R93") (pin "1") (pinfunction "1_1") (pintype "passive"))
      (node (ref "U8") (pin "14") (pinfunction "PA4_14") (pintype "passive"))
    )
    (net (code "13") (name "/LED3") (class "Default")
      (node (ref "R85") (pin "1") (pinfunction "1_1") (pintype "passive"))
      (node (ref "U8") (pin "16") (pinfunction "PA6_16") (pintype "passive"))
    )
    (net (code "14") (name "/LED4") (class "Default")
      (node (ref "R90") (pin "1") (pinfunction "1_1") (pintype "passive"))
      (node (ref "U8") (pin "15") (pinfunction "PA5_15") (pintype "passive"))
    )
    (net (code "15") (name "/MISO") (class "Default")
      (node (ref "R89") (pin "2") (pinfunction "2_2") (pintype "passive"))
      (node (ref "U3") (pin "44") (pinfunction "SDO(NC)_44") (pintype "passive"))
      (node (ref "U8") (pin "40") (pinfunction "PB4_40") (pintype "passive"))
    )
    (net (code "16") (name "/MOSI") (class "Default")
      (node (ref "U3") (pin "43") (pinfunction "SDI(NC)_43") (pintype "passive"))
      (node (ref "U8") (pin "41") (pinfunction "PB5_41") (pintype "passive"))
    )
    (net (code "17") (name "/SCK") (class "Default")
      (node (ref "U3") (pin "42") (pinfunction "SCK(IPA)_42") (pintype "passive"))
      (node (ref "U8") (pin "39") (pinfunction "PB3_39") (pintype "passive"))
    )
    (net (code "18") (name "/SCL") (class "Default")
      (node (ref "R80") (pin "2") (pinfunction "2_2") (pintype "passive"))
      (node (ref "U8") (pin "21") (pinfunction "PB10_21") (pintype "passive"))
    )
    (net (code "19") (name "/SDA") (class "Default")
      (node (ref "R79") (pin "2") (pinfunction "2_2") (pintype "passive"))
      (node (ref "U8") (pin "22") (pinfunction "PB11_22") (pintype "passive"))
    )
    (net (code "20") (name "/SWCLK") (class "Default")
      (node (ref "J10") (pin "1") (pinfunction "1_1") (pintype "passive"))
      (node (ref "U8") (pin "37") (pinfunction "PA14_37") (pintype "passive"))
    )
    (net (code "21") (name "/SWDIO") (class "Default")
      (node (ref "J10") (pin "2") (pinfunction "2_2") (pintype "passive"))
      (node (ref "U8") (pin "34") (pinfunction "PA13_34") (pintype "passive"))
    )
    (net (code "22") (name "/VEN_SNS") (class "Default")
      (node (ref "R102") (pin "1") (pinfunction "1_1") (pintype "passive"))
    )
    (net (code "23") (name "3V3") (class "Default")
      (node (ref "C47") (pin "2") (pinfunction "2_2") (pintype "passive"))
      (node (ref "C50") (pin "2") (pinfunction "2_2") (pintype "passive"))
      (node (ref "C51") (pin "2") (pinfunction "2_2") (pintype "passive"))
      (node (ref "C52") (pin "2") (pinfunction "2_2") (pintype "passive"))
      (node (ref "C53") (pin "2") (pinfunction "2_2") (pintype "passive"))
      (node (ref "C56") (pin "2") (pinfunction "2_2") (pintype "passive"))
      (node (ref "D1") (pin "1") (pinfunction "A_1") (pintype "passive"))
      (node (ref "D2") (pin "1") (pinfunction "A_1") (pintype "passive"))
      (node (ref "D3") (pin "1") (pinfunction "A_1") (pintype "passive"))
      (node (ref "D4") (pin "1") (pinfunction "A_1") (pintype "passive"))
      (node (ref "L2") (pin "1") (pinfunction "1_1") (pintype "passive"))
      (node (ref "R111") (pin "1") (pinfunction "1_1") (pintype "passive"))
      (node (ref "R81") (pin "2") (pinfunction "2_2") (pintype "passive"))
      (node (ref "R88") (pin "2") (pinfunction "2_2") (pintype "passive"))
      (node (ref "R89") (pin "1") (pinfunction "1_1") (pintype "passive"))
      (node (ref "U7") (pin "5") (pinfunction "Vio_5") (pintype "passive"))
      (node (ref "U8") (pin "1") (pinfunction "VBAT_1") (pintype "passive"))
      (node (ref "U8") (pin "24") (pinfunction "VDD_1_24") (pintype "passive"))
      (node (ref "U8") (pin "36") (pinfunction "VDD_2_36") (pintype "passive"))
      (node (ref "U8") (pin "48") (pinfunction "VDD_3_48") (pintype "passive"))
      (node (ref "U9") (pin "2") (pinfunction "VOUT_2") (pintype "passive"))
    )
    (net (code "24") (name "5V") (class "Default")
      (node (ref "C27") (pin "2") (pinfunction "2_2") (pintype "passive"))
      (node (ref "C29") (pin "2") (pinfunction "2_2") (pintype "passive"))
      (node (ref "C30") (pin "2") (pinfunction "2_2") (pintype "passive"))
      (node (ref "C31") (pin "2") (pinfunction "2_2") (pintype "passive"))
      (node (ref "C37") (pin "2") (pinfunction "2_2") (pintype "passive"))
      (node (ref "C48") (pin "2") (pinfunction "2_2") (pintype "passive"))
      (node (ref "L1") (pin "2") (pinfunction "2_2") (pintype "passive"))
      (node (ref "R77") (pin "1") (pinfunction "1_1") (pintype "passive"))
      (node (ref "R86") (pin "2") (pinfunction "2_2") (pintype "passive"))
      (node (ref "R87") (pin "2") (pinfunction "2_2") (pintype "passive"))
      (node (ref "U3") (pin "37") (pinfunction "VREG_37") (pintype "passive"))
      (node (ref "U4") (pin "4") (pinfunction "VCC_4") (pintype "passive"))
      (node (ref "U6") (pin "2") (pinfunction "+Vin_2") (pintype "passive"))
      (node (ref "U7") (pin "3") (pinfunction "Vcc_3") (pintype "passive"))
      (node (ref "U9") (pin "3") (pinfunction "VIN_3") (pintype "passive"))
    )
    (net (code "25") (name "5V_ISOL") (class "Default")
      (node (ref "C36") (pin "2") (pinfunction "2_2") (pintype "passive"))
      (node (ref "U2") (pin "37") (pinfunction "VREG_37") (pintype "passive"))
      (node (ref "U2") (pin "40") (pinfunction "ISOMD_40") (pintype "passive"))
      (node (ref "U6") (pin "4") (pinfunction "+Vo_4") (pintype "passive"))
    )
    (net (code "26") (name "C1") (class "Default")
      (node (ref "F2") (pin "2") (pinfunction "2_2") (pintype "passive"))
      (node (ref "Q24") (pin "2") (pinfunction "SOURCE_2") (pintype "passive"))
      (node (ref "R23") (pin "2") (pinfunction "2_2") (pintype "passive"))
      (node (ref "R49") (pin "1") (pinfunction "1_1") (pintype "passive"))
    )
    (net (code "27") (name "GND") (class "Default")
      (node (ref "C1") (pin "1") (pinfunction "1_1") (pintype "passive"))
      (node (ref "C25") (pin "1") (pinfunction "1_1") (pintype "passive"))
      (node (ref "C29") (pin "1") (pinfunction "1_1") (pintype "passive"))
      (node (ref "C30") (pin "1") (pinfunction "1_1") (pintype "passive"))
      (node (ref "C31") (pin "1") (pinfunction "1_1") (pintype "passive"))
      (node (ref "C33") (pin "1") (pinfunction "1_1") (pintype "passive"))
      (node (ref "C35") (pin "1") (pinfunction "1_1") (pintype "passive"))
      (node (ref "C37") (pin "1") (pinfunction "1_1") (pintype "passive"))
      (node (ref "C39") (pin "1") (pinfunction "1_1") (pintype "passive"))
      (node (ref "C41") (pin "1") (pinfunction "1_1") (pintype "passive"))
      (node (ref "C43") (pin "1") (pinfunction "1_1") (pintype "passive"))
      (node (ref "C44") (pin "1") (pinfunction "1_1") (pintype "passive"))
      (node (ref "C46") (pin "1") (pinfunction "1_1") (pintype "passive"))
      (node (ref "C47") (pin "1") (pinfunction "1_1") (pintype "passive"))
      (node (ref "C48") (pin "1") (pinfunction "1_1") (pintype "passive"))
      (node (ref "C49") (pin "2") (pinfunction "2_2") (pintype "passive"))
      (node (ref "C50") (pin "1") (pinfunction "1_1") (pintype "passive"))
      (node (ref "C51") (pin "1") (pinfunction "1_1") (pintype "passive"))
      (node (ref "C52") (pin "1") (pinfunction "1_1") (pintype "passive"))
      (node (ref "C53") (pin "1") (pinfunction "1_1") (pintype "passive"))
      (node (ref "C54") (pin "1") (pinfunction "1_1") (pintype "passive"))
      (node (ref "C55") (pin "1") (pinfunction "1_1") (pintype "passive"))
      (node (ref "C56") (pin "1") (pinfunction "1_1") (pintype "passive"))
      (node (ref "D10") (pin "1") (pinfunction "A_1") (pintype "passive"))
      (node (ref "D5") (pin "1") (pinfunction "+_1") (pintype "passive"))
      (node (ref "D7") (pin "2") (pinfunction "K_2") (pintype "passive"))
      (node (ref "D9") (pin "1") (pinfunction "A_1") (pintype "passive"))
      (node (ref "J10") (pin "3") (pinfunction "3_3") (pintype "passive"))
      (node (ref "J6") (pin "2") (pinfunction "2_2") (pintype "passive"))
      (node (ref "Q25") (pin "2") (pinfunction "SOURCE_2") (pintype "passive"))
      (node (ref "Q26") (pin "2") (pinfunction "SOURCE_2") (pintype "passive"))
      (node (ref "Q27") (pin "2") (pinfunction "SOURCE_2") (pintype "passive"))
      (node (ref "R100") (pin "1") (pinfunction "1_1") (pintype "passive"))
      (node (ref "R104") (pin "1") (pinfunction "1_1") (pintype "passive"))
      (node (ref "R109") (pin "1") (pinfunction "1_1") (pintype "passive"))
      (node (ref "R110") (pin "1") (pinfunction "1_1") (pintype "passive"))
      (node (ref "R24") (pin "2") (pinfunction "2_2") (pintype "passive"))
      (node (ref "R25") (pin "2") (pinfunction "2_2") (pintype "passive"))
      (node (ref "R75") (pin "1") (pinfunction "1_1") (pintype "passive"))
      (node (ref "R78") (pin "2") (pinfunction "2_2") (pintype "passive"))
      (node (ref "R92") (pin "1") (pinfunction "1_1") (pintype "passive"))
      (node (ref "U1") (pin "1") (pinfunction "GND_1") (pintype "power_in"))
      (node (ref "U1") (pin "9") (pinfunction "EP_9") (pintype "passive"))
      (node (ref "U3") (pin "30") (pinfunction "V-_30") (pintype "passive"))
      (node (ref "U3") (pin "31") (pinfunction "V-_31") (pintype "passive"))
      (node (ref "U3") (pin "40") (pinfunction "ISOMD_40") (pintype "passive"))
      (node (ref "U4") (pin "2") (pinfunction "GND_2") (pintype "passive"))
      (node (ref "U4") (pin "5") (pinfunction "WP_5") (pintype "passive"))
      (node (ref "U5") (pin "8") (pinfunction "VSS_8") (pintype "passive"))
      (node (ref "U6") (pin "1") (pinfunction "-Vin_1") (pintype "passive"))
      (node (ref "U7") (pin "2") (pinfunction "GND_2") (pintype "passive"))
      (node (ref "U7") (pin "8") (pinfunction "STB_8") (pintype "passive"))
      (node (ref "U7") (pin "9") (pinfunction "EP_9") (pintype "passive"))
      (node (ref "U8") (pin "23") (pinfunction "VSS_1_23") (pintype "passive"))
      (node (ref "U8") (pin "35") (pinfunction "VSS_2_35") (pintype "passive"))
      (node (ref "U8") (pin "44") (pinfunction "BOOT0_44") (pintype "passive"))
      (node (ref "U8") (pin "47") (pinfunction "VSS_3_47") (pintype "passive"))
      (node (ref "U8") (pin "8") (pinfunction "VSS_A_8") (pintype "passive"))
      (node (ref "U9") (pin "1") (pinfunction "VSS_1") (pintype "passive"))
    )
    (net (code "28") (name "MGND") (class "Default")
      (node (ref "C13") (pin "1") (pinfunction "1_1") (pintype "passive"))
      (node (ref "C32") (pin "1") (pinfunction "1_1") (pintype "passive"))
      (node (ref "C34") (pin "1") (pinfunction "1_1") (pintype "passive"))
      (node (ref "C36") (pin "1") (pinfunction "1_1") (pintype "passive"))
      (node (ref "C38") (pin "1") (pinfunction "1_1") (pintype "passive"))
      (node (ref "J5") (pin "2") (pinfunction "2_2") (pintype "passive"))
      (node (ref "Q13") (pin "2") (pinfunction "SOURCE_2") (pintype "passive"))
      (node (ref "R12") (pin "2") (pinfunction "2_2") (pintype "passive"))
      (node (ref "R38") (pin "1") (pinfunction "1_1") (pintype "passive"))
      (node (ref "R62") (pin "1") (pinfunction "1_1") (pintype "passive"))
      (node (ref "R91") (pin "1") (pinfunction "1_1") (pintype "passive"))
      (node (ref "U2") (pin "30") (pinfunction "V-_30") (pintype "passive"))
      (node (ref "U2") (pin "31") (pinfunction "V-_31") (pintype "passive"))
      (node (ref "U3") (pin "1") (pinfunction "V+_1") (pintype "passive"))
      (node (ref "U6") (pin "3") (pinfunction "0V_3") (pintype "passive"))
    )
    (net (code "29") (name "Net-(C27-Pad1)") (class "Default")
      (node (ref "C27") (pin "1") (pinfunction "1_1") (pintype "passive"))
      (node (ref "C28") (pin "2") (pinfunction "2_2") (pintype "passive"))
      (node (ref "R76") (pin "2") (pinfunction "2_2") (pintype "passive"))
    )
    (net (code "30") (name "Net-(D1-K)") (class "Default")
      (node (ref "D1") (pin "2") (pinfunction "K_2") (pintype "passive"))
      (node (ref "R85") (pin "2") (pinfunction "2_2") (pintype "passive"))
    )
    (net (code "31") (name "Net-(D2-K)") (class "Default")
      (node (ref "D2") (pin "2") (pinfunction "K_2") (pintype "passive"))
      (node (ref "R90") (pin "2") (pinfunction "2_2") (pintype "passive"))
    )
    (net (code "32") (name "Net-(D3-K)") (class "Default")
      (node (ref "D3") (pin "2") (pinfunction "K_2") (pintype "passive"))
      (node (ref "R93") (pin "2") (pinfunction "2_2") (pintype "passive"))
    )
    (net (code "33") (name "Net-(D4-K)") (class "Default")
      (node (ref "D4") (pin "2") (pinfunction "K_2") (pintype "passive"))
      (node (ref "R96") (pin "2") (pinfunction "2_2") (pintype "passive"))
    )
    (net (code "34") (name "Net-(D7-A)") (class "Default")
      (node (ref "D7") (pin "1") (pinfunction "A_1") (pintype "passive"))
      (node (ref "R107") (pin "1") (pinfunction "1_1") (pintype "passive"))
    )
    (net (code "35") (name "Net-(D8-+)") (class "Default")
      (node (ref "D8") (pin "1") (pinfunction "+_1") (pintype "passive"))
      (node (ref "Q28") (pin "1") (pinfunction "GATE_1") (pintype "passive"))
      (node (ref "R105") (pin "1") (pinfunction "1_1") (pintype "passive"))
      (node (ref "R106") (pin "2") (pinfunction "2_2") (pintype "passive"))
    )
    (net (code "36") (name "Net-(Q1-DRAIN)") (class "Default")
      (node (ref "Q1") (pin "3") (pinfunction "DRAIN_3") (pintype "passive"))
      (node (ref "R1") (pin "1") (pinfunction "1_1") (pintype "passive"))
    )
    (net (code "37") (name "Net-(Q1-GATE)") (class "Default")
      (node (ref "Q1") (pin "1") (pinfunction "GATE_1") (pintype "passive"))
      (node (ref "R50") (pin "1") (pinfunction "1_1") (pintype "passive"))
    )
    (net (code "38") (name "Net-(Q2-DRAIN)") (class "Default")
      (node (ref "Q2") (pin "3") (pinfunction "DRAIN_3") (pintype "passive"))
      (node (ref "R2") (pin "1") (pinfunction "1_1") (pintype "passive"))
    )
    (net (code "39") (name "Net-(Q2-GATE)") (class "Default")
      (node (ref "Q2") (pin "1") (pinfunction "GATE_1") (pintype "passive"))
      (node (ref "R51") (pin "1") (pinfunction "1_1") (pintype "passive"))
    )
    (net (code "40") (name "Net-(Q2-SOURCE)") (class "Default")
      (node (ref "Q2") (pin "2") (pinfunction "SOURCE_2") (pintype "passive"))
      (node (ref "R1") (pin "2") (pinfunction "2_2") (pintype "passive"))
      (node (ref "R27") (pin "1") (pinfunction "1_1") (pintype "passive"))
    )
    (net (code "41") (name "Net-(Q3-DRAIN)") (class "Default")
      (node (ref "Q3") (pin "3") (pinfunction "DRAIN_3") (pintype "passive"))
      (node (ref "R3") (pin "1") (pinfunction "1_1") (pintype "passive"))
    )
    (net (code "42") (name "Net-(Q3-GATE)") (class "Default")
      (node (ref "Q3") (pin "1") (pinfunction "GATE_1") (pintype "passive"))
      (node (ref "R52") (pin "1") (pinfunction "1_1") (pintype "passive"))
    )
    (net (code "43") (name "Net-(Q3-SOURCE)") (class "Default")
      (node (ref "Q3") (pin "2") (pinfunction "SOURCE_2") (pintype "passive"))
      (node (ref "R2") (pin "2") (pinfunction "2_2") (pintype "passive"))
      (node (ref "R28") (pin "1") (pinfunction "1_1") (pintype "passive"))
    )
    (net (code "44") (name "Net-(Q4-DRAIN)") (class "Default")
      (node (ref "Q4") (pin "3") (pinfunction "DRAIN_3") (pintype "passive"))
      (node (ref "R4") (pin "1") (pinfunction "1_1") (pintype "passive"))
    )
    (net (code "45") (name "Net-(Q4-GATE)") (class "Default")
      (node (ref "Q4") (pin "1") (pinfunction "GATE_1") (pintype "passive"))
      (node (ref "R53") (pin "1") (pinfunction "1_1") (pintype "passive"))
    )
    (net (code "46") (name "Net-(Q4-SOURCE)") (class "Default")
      (node (ref "Q4") (pin "2") (pinfunction "SOURCE_2") (pintype "passive"))
      (node (ref "R29") (pin "1") (pinfunction "1_1") (pintype "passive"))
      (node (ref "R3") (pin "2") (pinfunction "2_2") (pintype "passive"))
    )
    (net (code "47") (name "Net-(Q5-DRAIN)") (class "Default")
      (node (ref "Q5") (pin "3") (pinfunction "DRAIN_3") (pintype "passive"))
      (node (ref "R5") (pin "1") (pinfunction "1_1") (pintype "passive"))
    )
    (net (code "48") (name "Net-(Q5-GATE)") (class "Default")
      (node (ref "Q5") (pin "1") (pinfunction "GATE_1") (pintype "passive"))
      (node (ref "R54") (pin "1") (pinfunction "1_1") (pintype "passive"))
    )
    (net (code "49") (name "Net-(Q5-SOURCE)") (class "Default")
      (node (ref "Q5") (pin "2") (pinfunction "SOURCE_2") (pintype "passive"))
      (node (ref "R30") (pin "1") (pinfunction "1_1") (pintype "passive"))
      (node (ref "R4") (pin "2") (pinfunction "2_2") (pintype "passive"))
    )
    (net (code "50") (name "Net-(Q6-DRAIN)") (class "Default")
      (node (ref "Q6") (pin "3") (pinfunction "DRAIN_3") (pintype "passive"))
      (node (ref "R6") (pin "1") (pinfunction "1_1") (pintype "passive"))
    )
    (net (code "51") (name "Net-(Q6-GATE)") (class "Default")
      (node (ref "Q6") (pin "1") (pinfunction "GATE_1") (pintype "passive"))
      (node (ref "R55") (pin "1") (pinfunction "1_1") (pintype "passive"))
    )
    (net (code "52") (name "Net-(Q6-SOURCE)") (class "Default")
      (node (ref "Q6") (pin "2") (pinfunction "SOURCE_2") (pintype "passive"))
      (node (ref "R31") (pin "1") (pinfunction "1_1") (pintype "passive"))
      (node (ref "R5") (pin "2") (pinfunction "2_2") (pintype "passive"))
    )
    (net (code "53") (name "Net-(Q7-DRAIN)") (class "Default")
      (node (ref "Q7") (pin "3") (pinfunction "DRAIN_3") (pintype "passive"))
      (node (ref "R7") (pin "1") (pinfunction "1_1") (pintype "passive"))
    )
    (net (code "54") (name "Net-(Q7-GATE)") (class "Default")
      (node (ref "Q7") (pin "1") (pinfunction "GATE_1") (pintype "passive"))
      (node (ref "R56") (pin "1") (pinfunction "1_1") (pintype "passive"))
    )
    (net (code "55") (name "Net-(Q7-SOURCE)") (class "Default")
      (node (ref "Q7") (pin "2") (pinfunction "SOURCE_2") (pintype "passive"))
      (node (ref "R32") (pin "1") (pinfunction "1_1") (pintype "passive"))
      (node (ref "R6") (pin "2") (pinfunction "2_2") (pintype "passive"))
    )
    (net (code "56") (name "Net-(Q8-DRAIN)") (class "Default")
      (node (ref "Q8") (pin "3") (pinfunction "DRAIN_3") (pintype "passive"))
      (node (ref "R8") (pin "1") (pinfunction "1_1") (pintype "passive"))
    )
    (net (code "57") (name "Net-(Q8-GATE)") (class "Default")
      (node (ref "Q8") (pin "1") (pinfunction "GATE_1") (pintype "passive"))
      (node (ref "R57") (pin "1") (pinfunction "1_1") (pintype "passive"))
    )
    (net (code "58") (name "Net-(Q8-SOURCE)") (class "Default")
      (node (ref "Q8") (pin "2") (pinfunction "SOURCE_2") (pintype "passive"))
      (node (ref "R33") (pin "1") (pinfunction "1_1") (pintype "passive"))
      (node (ref "R7") (pin "2") (pinfunction "2_2") (pintype "passive"))
    )
    (net (code "59") (name "Net-(Q9-DRAIN)") (class "Default")
      (node (ref "Q9") (pin "3") (pinfunction "DRAIN_3") (pintype "passive"))
      (node (ref "R9") (pin "1") (pinfunction "1_1") (pintype "passive"))
    )
    (net (code "60") (name "Net-(Q9-GATE)") (class "Default")
      (node (ref "Q9") (pin "1") (pinfunction "GATE_1") (pintype "passive"))
      (node (ref "R58") (pin "1") (pinfunction "1_1") (pintype "passive"))
    )
    (net (code "61") (name "Net-(Q9-SOURCE)") (class "Default")
      (node (ref "Q9") (pin "2") (pinfunction "SOURCE_2") (pintype "passive"))
      (node (ref "R34") (pin "1") (pinfunction "1_1") (pintype "passive"))
      (node (ref "R8") (pin "2") (pinfunction "2_2") (pintype "passive"))
    )
    (net (code "62") (name "Net-(Q10-DRAIN)") (class "Default")
      (node (ref "Q10") (pin "3") (pinfunction "DRAIN_3") (pintype "passive"))
      (node (ref "R10") (pin "1") (pinfunction "1_1") (pintype "passive"))
    )
    (net (code "63") (name "Net-(Q10-GATE)") (class "Default")
      (node (ref "Q10") (pin "1") (pinfunction "GATE_1") (pintype "passive"))
      (node (ref "R59") (pin "1") (pinfunction "1_1") (pintype "passive"))
    )
    (net (code "64") (name "Net-(Q10-SOURCE)") (class "Default")
      (node (ref "Q10") (pin "2") (pinfunction "SOURCE_2") (pintype "passive"))
      (node (ref "R35") (pin "1") (pinfunction "1_1") (pintype "passive"))
      (node (ref "R9") (pin "2") (pinfunction "2_2") (pintype "passive"))
    )
    (net (code "65") (name "Net-(Q11-DRAIN)") (class "Default")
      (node (ref "Q11") (pin "3") (pinfunction "DRAIN_3") (pintype "passive"))
      (node (ref "R11") (pin "1") (pinfunction "1_1") (pintype "passive"))
    )
    (net (code "66") (name "Net-(Q11-GATE)") (class "Default")
      (node (ref "Q11") (pin "1") (pinfunction "GATE_1") (pintype "passive"))
      (node (ref "R60") (pin "1") (pinfunction "1_1") (pintype "passive"))
    )
    (net (code "67") (name "Net-(Q11-SOURCE)") (class "Default")
      (node (ref "Q11") (pin "2") (pinfunction "SOURCE_2") (pintype "passive"))
      (node (ref "R10") (pin "2") (pinfunction "2_2") (pintype "passive"))
      (node (ref "R36") (pin "1") (pinfunction "1_1") (pintype "passive"))
    )
    (net (code "68") (name "Net-(Q12-DRAIN)") (class "Default")
      (node (ref "Q12") (pin "3") (pinfunction "DRAIN_3") (pintype "passive"))
      (node (ref "R12") (pin "1") (pinfunction "1_1") (pintype "passive"))
    )
    (net (code "69") (name "Net-(Q12-GATE)") (class "Default")
      (node (ref "Q12") (pin "1") (pinfunction "GATE_1") (pintype "passive"))
      (node (ref "R61") (pin "1") (pinfunction "1_1") (pintype "passive"))
    )
    (net (code "70") (name "Net-(Q12-SOURCE)") (class "Default")
      (node (ref "Q12") (pin "2") (pinfunction "SOURCE_2") (pintype "passive"))
      (node (ref "R11") (pin "2") (pinfunction "2_2") (pintype "passive"))
      (node (ref "R37") (pin "1") (pinfunction "1_1") (pintype "passive"))
    )
    (net (code "71") (name "Net-(Q13-DRAIN)") (class "Default")
      (node (ref "Q13") (pin "3") (pinfunction "DRAIN_3") (pintype "passive"))
      (node (ref "R13") (pin "1") (pinfunction "1_1") (pintype "passive"))
    )
    (net (code "72") (name "Net-(Q13-GATE)") (class "Default")
      (node (ref "Q13") (pin "1") (pinfunction "GATE_1") (pintype "passive"))
      (node (ref "R63") (pin "1") (pinfunction "1_1") (pintype "passive"))
    )
    (net (code "73") (name "Net-(Q14-DRAIN)") (class "Default")
      (node (ref "Q14") (pin "3") (pinfunction "DRAIN_3") (pintype "passive"))
      (node (ref "R14") (pin "1") (pinfunction "1_1") (pintype "passive"))
    )
    (net (code "74") (name "Net-(Q14-GATE)") (class "Default")
      (node (ref "Q14") (pin "1") (pinfunction "GATE_1") (pintype "passive"))
      (node (ref "R64") (pin "1") (pinfunction "1_1") (pintype "passive"))
    )
    (net (code "75") (name "Net-(Q14-SOURCE)") (class "Default")
      (node (ref "Q14") (pin "2") (pinfunction "SOURCE_2") (pintype "passive"))
      (node (ref "R13") (pin "2") (pinfunction "2_2") (pintype "passive"))
      (node (ref "R39") (pin "1") (pinfunction "1_1") (pintype "passive"))
    )
    (net (code "76") (name "Net-(Q15-DRAIN)") (class "Default")
      (node (ref "Q15") (pin "3") (pinfunction "DRAIN_3") (pintype "passive"))
      (node (ref "R15") (pin "1") (pinfunction "1_1") (pintype "passive"))
    )
    (net (code "77") (name "Net-(Q15-GATE)") (class "Default")
      (node (ref "Q15") (pin "1") (pinfunction "GATE_1") (pintype "passive"))
      (node (ref "R65") (pin "1") (pinfunction "1_1") (pintype "passive"))
    )
    (net (code "78") (name "Net-(Q15-SOURCE)") (class "Default")
      (node (ref "Q15") (pin "2") (pinfunction "SOURCE_2") (pintype "passive"))
      (node (ref "R14") (pin "2") (pinfunction "2_2") (pintype "passive"))
      (node (ref "R40") (pin "1") (pinfunction "1_1") (pintype "passive"))
    )
    (net (code "79") (name "Net-(Q16-DRAIN)") (class "Default")
      (node (ref "Q16") (pin "3") (pinfunction "DRAIN_3") (pintype "passive"))
      (node (ref "R16") (pin "1") (pinfunction "1_1") (pintype "passive"))
    )
    (net (code "80") (name "Net-(Q16-GATE)") (class "Default")
      (node (ref "Q16") (pin "1") (pinfunction "GATE_1") (pintype "passive"))
      (node (ref "R66") (pin "1") (pinfunction "1_1") (pintype "passive"))
    )
    (net (code "81") (name "Net-(Q16-SOURCE)") (class "Default")
      (node (ref "Q16") (pin "2") (pinfunction "SOURCE_2") (pintype "passive"))
      (node (ref "R15") (pin "2") (pinfunction "2_2") (pintype "passive"))
      (node (ref "R41") (pin "1") (pinfunction "1_1") (pintype "passive"))
    )
    (net (code "82") (name "Net-(Q17-DRAIN)") (class "Default")
      (node (ref "Q17") (pin "3") (pinfunction "DRAIN_3") (pintype "passive"))
      (node (ref "R17") (pin "1") (pinfunction "1_1") (pintype "passive"))
    )
    (net (code "83") (name "Net-(Q17-GATE)") (class "Default")
      (node (ref "Q17") (pin "1") (pinfunction "GATE_1") (pintype "passive"))
      (node (ref "R67") (pin "1") (pinfunction "1_1") (pintype "passive"))
    )
    (net (code "84") (name "Net-(Q17-SOURCE)") (class "Default")
      (node (ref "Q17") (pin "2") (pinfunction "SOURCE_2") (pintype "passive"))
      (node (ref "R16") (pin "2") (pinfunction "2_2") (pintype "passive"))
      (node (ref "R42") (pin "1") (pinfunction "1_1") (pintype "passive"))
    )
    (net (code "85") (name "Net-(Q18-DRAIN)") (class "Default")
      (node (ref "Q18") (pin "3") (pinfunction "DRAIN_3") (pintype "passive"))
      (node (ref "R18") (pin "1") (pinfunction "1_1") (pintype "passive"))
    )
    (net (code "86") (name "Net-(Q18-GATE)") (class "Default")
      (node (ref "Q18") (pin "1") (pinfunction "GATE_1") (pintype "passive"))
      (node (ref "R68") (pin "1") (pinfunction "1_1") (pintype "passive"))
    )
    (net (code "87") (name "Net-(Q18-SOURCE)") (class "Default")
      (node (ref "Q18") (pin "2") (pinfunction "SOURCE_2") (pintype "passive"))
      (node (ref "R17") (pin "2") (pinfunction "2_2") (pintype "passive"))
      (node (ref "R43") (pin "1") (pinfunction "1_1") (pintype "passive"))
    )
    (net (code "88") (name "Net-(Q19-DRAIN)") (class "Default")
      (node (ref "Q19") (pin "3") (pinfunction "DRAIN_3") (pintype "passive"))
      (node (ref "R19") (pin "1") (pinfunction "1_1") (pintype "passive"))
    )
    (net (code "89") (name "Net-(Q19-GATE)") (class "Default")
      (node (ref "Q19") (pin "1") (pinfunction "GATE_1") (pintype "passive"))
      (node (ref "R69") (pin "1") (pinfunction "1_1") (pintype "passive"))
    )
    (net (code "90") (name "Net-(Q19-SOURCE)") (class "Default")
      (node (ref "Q19") (pin "2") (pinfunction "SOURCE_2") (pintype "passive"))
      (node (ref "R18") (pin "2") (pinfunction "2_2") (pintype "passive"))
      (node (ref "R44") (pin "1") (pinfunction "1_1") (pintype "passive"))
    )
    (net (code "91") (name "Net-(Q20-DRAIN)") (class "Default")
      (node (ref "Q20") (pin "3") (pinfunction "DRAIN_3") (pintype "passive"))
      (node (ref "R20") (pin "1") (pinfunction "1_1") (pintype "passive"))
    )
    (net (code "92") (name "Net-(Q20-GATE)") (class "Default")
      (node (ref "Q20") (pin "1") (pinfunction "GATE_1") (pintype "passive"))
      (node (ref "R70") (pin "1") (pinfunction "1_1") (pintype "passive"))
    )
    (net (code "93") (name "Net-(Q20-SOURCE)") (class "Default")
      (node (ref "Q20") (pin "2") (pinfunction "SOURCE_2") (pintype "passive"))
      (node (ref "R19") (pin "2") (pinfunction "2_2") (pintype "passive"))
      (node (ref "R45") (pin "1") (pinfunction "1_1") (pintype "passive"))
    )
    (net (code "94") (name "Net-(Q21-DRAIN)") (class "Default")
      (node (ref "Q21") (pin "3") (pinfunction "DRAIN_3") (pintype "passive"))
      (node (ref "R21") (pin "1") (pinfunction "1_1") (pintype "passive"))
    )
    (net (code "95") (name "Net-(Q21-GATE)") (class "Default")
      (node (ref "Q21") (pin "1") (pinfunction "GATE_1") (pintype "passive"))
      (node (ref "R71") (pin "1") (pinfunction "1_1") (pintype "passive"))
    )
    (net (code "96") (name "Net-(Q21-SOURCE)") (class "Default")
      (node (ref "Q21") (pin "2") (pinfunction "SOURCE_2") (pintype "passive"))
      (node (ref "R20") (pin "2") (pinfunction "2_2") (pintype "passive"))
      (node (ref "R46") (pin "1") (pinfunction "1_1") (pintype "passive"))
    )
    (net (code "97") (name "Net-(Q22-DRAIN)") (class "Default")
      (node (ref "Q22") (pin "3") (pinfunction "DRAIN_3") (pintype "passive"))
      (node (ref "R22") (pin "1") (pinfunction "1_1") (pintype "passive"))
    )
    (net (code "98") (name "Net-(Q22-GATE)") (class "Default")
      (node (ref "Q22") (pin "1") (pinfunction "GATE_1") (pintype "passive"))
      (node (ref "R72") (pin "1") (pinfunction "1_1") (pintype "passive"))
    )
    (net (code "99") (name "Net-(Q22-SOURCE)") (class "Default")
      (node (ref "Q22") (pin "2") (pinfunction "SOURCE_2") (pintype "passive"))
      (node (ref "R21") (pin "2") (pinfunction "2_2") (pintype "passive"))
      (node (ref "R47") (pin "1") (pinfunction "1_1") (pintype "passive"))
    )
    (net (code "100") (name "Net-(Q23-DRAIN)") (class "Default")
      (node (ref "Q23") (pin "3") (pinfunction "DRAIN_3") (pintype "passive"))
      (node (ref "R23") (pin "1") (pinfunction "1_1") (pintype "passive"))
    )
    (net (code "101") (name "Net-(Q23-GATE)") (class "Default")
      (node (ref "Q23") (pin "1") (pinfunction "GATE_1") (pintype "passive"))
      (node (ref "R73") (pin "1") (pinfunction "1_1") (pintype "passive"))
    )
    (net (code "102") (name "Net-(Q23-SOURCE)") (class "Default")
      (node (ref "Q23") (pin "2") (pinfunction "SOURCE_2") (pintype "passive"))
      (node (ref "R22") (pin "2") (pinfunction "2_2") (pintype "passive"))
      (node (ref "R48") (pin "1") (pinfunction "1_1") (pintype "passive"))
    )
    (net (code "103") (name "Net-(Q24-DRAIN)") (class "Default")
      (node (ref "Q24") (pin "3") (pinfunction "DRAIN_3") (pintype "passive"))
      (node (ref "R24") (pin "1") (pinfunction "1_1") (pintype "passive"))
    )
    (net (code "104") (name "Net-(Q24-GATE)") (class "Default")
      (node (ref "Q24") (pin "1") (pinfunction "GATE_1") (pintype "passive"))
      (node (ref "R74") (pin "1") (pinfunction "1_1") (pintype "passive"))
    )
    (net (code "105") (name "Net-(Q25-GATE)") (class "Default")
      (node (ref "Q25") (pin "1") (pinfunction "GATE_1") (pintype "passive"))
      (node (ref "U5") (pin "3") (pinfunction "P1_3") (pintype "passive"))
    )
    (net (code "106") (name "Net-(Q26-GATE)") (class "Default")
      (node (ref "Q26") (pin "1") (pinfunction "GATE_1") (pintype "passive"))
      (node (ref "U5") (pin "1") (pinfunction "P2_1") (pintype "passive"))
    )
    (net (code "107") (name "Net-(Q27-DRAIN)") (class "Default")
      (node (ref "Q27") (pin "3") (pinfunction "DRAIN_3") (pintype "passive"))
      (node (ref "R106") (pin "1") (pinfunction "1_1") (pintype "passive"))
    )
    (net (code "108") (name "Net-(Q27-GATE)") (class "Default")
      (node (ref "Q27") (pin "1") (pinfunction "GATE_1") (pintype "passive"))
      (node (ref "R101") (pin "1") (pinfunction "1_1") (pintype "passive"))
    )
    (net (code "109") (name "Net-(Q28-DRAIN)") (class "Default")
      (node (ref "Q28") (pin "3") (pinfunction "DRAIN_3") (pintype "passive"))
      (node (ref "R108") (pin "2") (pinfunction "2_2") (pintype "passive"))
    )
    (net (code "110") (name "Net-(R99-Pad2)") (class "Default")
      (node (ref "R99") (pin "2") (pinfunction "2_2") (pintype "passive"))
      (node (ref "SW1") (pin "3") (pinfunction "3_3") (pintype "passive"))
      (node (ref "SW1") (pin "4") (pinfunction "4_4") (pintype "passive"))
    )
    (net (code "111") (name "Net-(R103-Pad1)") (class "Default")
      (node (ref "R103") (pin "1") (pinfunction "1_1") (pintype "passive"))
      (node (ref "R110") (pin "2") (pinfunction "2_2") (pintype "passive"))
    )
    (net (code "112") (name "Net-(U1-BST)") (class "Default")
      (node (ref "C26") (pin "1") (pinfunction "1_1") (pintype "passive"))
      (node (ref "U1") (pin "7") (pinfunction "BST_7") (pintype "passive"))
    )
    (net (code "113") (name "Net-(U1-FB)") (class "Default")
      (node (ref "C28") (pin "1") (pinfunction "1_1") (pintype "passive"))
      (node (ref "R77") (pin "2") (pinfunction "2_2") (pintype "passive"))
      (node (ref "R78") (pin "1") (pinfunction "1_1") (pintype "passive"))
      (node (ref "U1") (pin "5") (pinfunction "FB_5") (pintype "power_in"))
    )
    (net (code "114") (name "Net-(U1-RON)") (class "Default")
      (node (ref "R25") (pin "1") (pinfunction "1_1") (pintype "passive"))
      (node (ref "U1") (pin "4") (pinfunction "RON_4") (pintype "power_in"))
    )
    (net (code "115") (name "Net-(U1-SW)") (class "Default")
      (node (ref "C26") (pin "2") (pinfunction "2_2") (pintype "passive"))
      (node (ref "L1") (pin "1") (pinfunction "1_1") (pintype "passive"))
      (node (ref "R76") (pin "1") (pinfunction "1_1") (pintype "passive"))
      (node (ref "U1") (pin "8") (pinfunction "SW_8") (pintype "power_in"))
    )
    (net (code "116") (name "Net-(U2-C0)") (class "Default")
      (node (ref "R62") (pin "2") (pinfunction "2_2") (pintype "passive"))
      (node (ref "U2") (pin "26") (pinfunction "C0_26") (pintype "passive"))
    )
    (net (code "117") (name "Net-(U2-C1)") (class "Default")
      (node (ref "C12") (pin "1") (pinfunction "1_1") (pintype "passive"))
      (node (ref "C13") (pin "2") (pinfunction "2_2") (pintype "passive"))
      (node (ref "R37") (pin "2") (pinfunction "2_2") (pintype "passive"))
      (node (ref "U2") (pin "24") (pinfunction "C1_24") (pintype "passive"))
    )
    (net (code "118") (name "Net-(U2-C2)") (class "Default")
      (node (ref "C11") (pin "1") (pinfunction "1_1") (pintype "passive"))
      (node (ref "C12") (pin "2") (pinfunction "2_2") (pintype "passive"))
      (node (ref "R36") (pin "2") (pinfunction "2_2") (pintype "passive"))
      (node (ref "U2") (pin "22") (pinfunction "C2_22") (pintype "passive"))
    )
    (net (code "119") (name "Net-(U2-C3)") (class "Default")
      (node (ref "C10") (pin "1") (pinfunction "1_1") (pintype "passive"))
      (node (ref "C11") (pin "2") (pinfunction "2_2") (pintype "passive"))
      (node (ref "R35") (pin "2") (pinfunction "2_2") (pintype "passive"))
      (node (ref "U2") (pin "20") (pinfunction "C3_20") (pintype "passive"))
    )
    (net (code "120") (name "Net-(U2-C4)") (class "Default")
      (node (ref "C10") (pin "2") (pinfunction "2_2") (pintype "passive"))
      (node (ref "C9") (pin "1") (pinfunction "1_1") (pintype "passive"))
      (node (ref "R34") (pin "2") (pinfunction "2_2") (pintype "passive"))
      (node (ref "U2") (pin "18") (pinfunction "C4_18") (pintype "passive"))
    )
    (net (code "121") (name "Net-(U2-C5)") (class "Default")
      (node (ref "C8") (pin "1") (pinfunction "1_1") (pintype "passive"))
      (node (ref "C9") (pin "2") (pinfunction "2_2") (pintype "passive"))
      (node (ref "R33") (pin "2") (pinfunction "2_2") (pintype "passive"))
      (node (ref "U2") (pin "16") (pinfunction "C5_16") (pintype "passive"))
    )
    (net (code "122") (name "Net-(U2-C6)") (class "Default")
      (node (ref "C7") (pin "1") (pinfunction "1_1") (pintype "passive"))
      (node (ref "C8") (pin "2") (pinfunction "2_2") (pintype "passive"))
      (node (ref "R32") (pin "2") (pinfunction "2_2") (pintype "passive"))
      (node (ref "U2") (pin "14") (pinfunction "C6_14") (pintype "passive"))
    )
    (net (code "123") (name "Net-(U2-C7)") (class "Default")
      (node (ref "C6") (pin "1") (pinfunction "1_1") (pintype "passive"))
      (node (ref "C7") (pin "2") (pinfunction "2_2") (pintype "passive"))
      (node (ref "R31") (pin "2") (pinfunction "2_2") (pintype "passive"))
      (node (ref "U2") (pin "12") (pinfunction "C7_12") (pintype "passive"))
    )
    (net (code "124") (name "Net-(U2-C8)") (class "Default")
      (node (ref "C5") (pin "1") (pinfunction "1_1") (pintype "passive"))
      (node (ref "C6") (pin "2") (pinfunction "2_2") (pintype "passive"))
      (node (ref "R30") (pin "2") (pinfunction "2_2") (pintype "passive"))
      (node (ref "U2") (pin "10") (pinfunction "C8_10") (pintype "passive"))
    )
    (net (code "125") (name "Net-(U2-C9)") (class "Default")
      (node (ref "C4") (pin "1") (pinfunction "1_1") (pintype "passive"))
      (node (ref "C5") (pin "2") (pinfunction "2_2") (pintype "passive"))
      (node (ref "R29") (pin "2") (pinfunction "2_2") (pintype "passive"))
      (node (ref "U2") (pin "8") (pinfunction "C9_8") (pintype "passive"))
    )
    (net (code "126") (name "Net-(U2-C10)") (class "Default")
      (node (ref "C3") (pin "1") (pinfunction "1_1") (pintype "passive"))
      (node (ref "C4") (pin "2") (pinfunction "2_2") (pintype "passive"))
      (node (ref "R28") (pin "2") (pinfunction "2_2") (pintype "passive"))
      (node (ref "U2") (pin "6") (pinfunction "C10_6") (pintype "passive"))
    )
    (net (code "127") (name "Net-(U2-C11)") (class "Default")
      (node (ref "C2") (pin "1") (pinfunction "1_1") (pintype "passive"))
      (node (ref "C3") (pin "2") (pinfunction "2_2") (pintype "passive"))
      (node (ref "R27") (pin "2") (pinfunction "2_2") (pintype "passive"))
      (node (ref "U2") (pin "4") (pinfunction "C11_4") (pintype "passive"))
    )
    (net (code "128") (name "Net-(U2-C12)") (class "Default")
      (node (ref "C2") (pin "2") (pinfunction "2_2") (pintype "passive"))
      (node (ref "R26") (pin "2") (pinfunction "2_2") (pintype "passive"))
      (node (ref "U2") (pin "2") (pinfunction "C12_2") (pintype "passive"))
    )
    (net (code "129") (name "Net-(U2-CSB(IMA))") (class "Default")
      (node (ref "C40") (pin "2") (pinfunction "2_2") (pintype "passive"))
      (node (ref "R97") (pin "2") (pinfunction "2_2") (pintype "passive"))
      (node (ref "U2") (pin "41") (pinfunction "CSB(IMA)_41") (pintype "passive"))
    )
    (net (code "130") (name "Net-(U2-DTEN)") (class "Default")
      (node (ref "J2") (pin "1") (pinfunction "1_1") (pintype "passive"))
      (node (ref "U2") (pin "36") (pinfunction "DTEN_36") (pintype "passive"))
    )
    (net (code "131") (name "Net-(U2-GPI03)") (class "Default")
      (node (ref "C38") (pin "2") (pinfunction "2_2") (pintype "passive"))
      (node (ref "J5") (pin "1") (pinfunction "1_1") (pintype "passive"))
      (node (ref "R94") (pin "2") (pinfunction "2_2") (pintype "passive"))
      (node (ref "U2") (pin "29") (pinfunction "GPI03_29") (pintype "passive"))
    )
    (net (code "132") (name "Net-(U2-IBIAS)") (class "Default")
      (node (ref "R83") (pin "2") (pinfunction "2_2") (pintype "passive"))
      (node (ref "U2") (pin "45") (pinfunction "IBIAS_45") (pintype "passive"))
    )
    (net (code "133") (name "Net-(U2-ICMP)") (class "Default")
      (node (ref "R83") (pin "1") (pinfunction "1_1") (pintype "passive"))
      (node (ref "R91") (pin "2") (pinfunction "2_2") (pintype "passive"))
      (node (ref "U2") (pin "46") (pinfunction "ICMP_46") (pintype "passive"))
    )
    (net (code "134") (name "Net-(U2-IMB)") (class "Default")
      (node (ref "R82") (pin "1") (pinfunction "1_1") (pintype "passive"))
      (node (ref "U2") (pin "47") (pinfunction "IMB_47") (pintype "passive"))
    )
    (net (code "135") (name "Net-(U2-IPB)") (class "Default")
      (node (ref "R82") (pin "2") (pinfunction "2_2") (pintype "passive"))
      (node (ref "U2") (pin "48") (pinfunction "IPB_48") (pintype "passive"))
    )
    (net (code "136") (name "Net-(U2-S1)") (class "Default")
      (node (ref "R61") (pin "2") (pinfunction "2_2") (pintype "passive"))
      (node (ref "U2") (pin "25") (pinfunction "S1_25") (pintype "passive"))
    )
    (net (code "137") (name "Net-(U2-S2)") (class "Default")
      (node (ref "R60") (pin "2") (pinfunction "2_2") (pintype "passive"))
      (node (ref "U2") (pin "23") (pinfunction "S2_23") (pintype "passive"))
    )
    (net (code "138") (name "Net-(U2-S3)") (class "Default")
      (node (ref "R59") (pin "2") (pinfunction "2_2") (pintype "passive"))
      (node (ref "U2") (pin "21") (pinfunction "S3_21") (pintype "passive"))
    )
    (net (code "139") (name "Net-(U2-S4)") (class "Default")
      (node (ref "R58") (pin "2") (pinfunction "2_2") (pintype "passive"))
      (node (ref "U2") (pin "19") (pinfunction "S4_19") (pintype "passive"))
    )
    (net (code "140") (name "Net-(U2-S5)") (class "Default")
      (node (ref "R57") (pin "2") (pinfunction "2_2") (pintype "passive"))
      (node (ref "U2") (pin "17") (pinfunction "S5_17") (pintype "passive"))
    )
    (net (code "141") (name "Net-(U2-S6)") (class "Default")
      (node (ref "R56") (pin "2") (pinfunction "2_2") (pintype "passive"))
      (node (ref "U2") (pin "15") (pinfunction "S6_15") (pintype "passive"))
    )
    (net (code "142") (name "Net-(U2-S7)") (class "Default")
      (node (ref "R55") (pin "2") (pinfunction "2_2") (pintype "passive"))
      (node (ref "U2") (pin "13") (pinfunction "S7_13") (pintype "passive"))
    )
    (net (code "143") (name "Net-(U2-S8)") (class "Default")
      (node (ref "R54") (pin "2") (pinfunction "2_2") (pintype "passive"))
      (node (ref "U2") (pin "11") (pinfunction "S8_11") (pintype "passive"))
    )
    (net (code "144") (name "Net-(U2-S9)") (class "Default")
      (node (ref "R53") (pin "2") (pinfunction "2_2") (pintype "passive"))
      (node (ref "U2") (pin "9") (pinfunction "S9_9") (pintype "passive"))
    )
    (net (code "145") (name "Net-(U2-S10)") (class "Default")
      (node (ref "R52") (pin "2") (pinfunction "2_2") (pintype "passive"))
      (node (ref "U2") (pin "7") (pinfunction "S10_7") (pintype "passive"))
    )
    (net (code "146") (name "Net-(U2-S11)") (class "Default")
      (node (ref "R51") (pin "2") (pinfunction "2_2") (pintype "passive"))
      (node (ref "U2") (pin "5") (pinfunction "S11_5") (pintype "passive"))
    )
    (net (code "147") (name "Net-(U2-S12)") (class "Default")
      (node (ref "R50") (pin "2") (pinfunction "2_2") (pintype "passive"))
      (node (ref "U2") (pin "3") (pinfunction "S12_3") (pintype "passive"))
    )
    (net (code "148") (name "Net-(U2-SCK(IPA))") (class "Default")
      (node (ref "C42") (pin "2") (pinfunction "2_2") (pintype "passive"))
      (node (ref "R97") (pin "1") (pinfunction "1_1") (pintype "passive"))
      (node (ref "U2") (pin "42") (pinfunction "SCK(IPA)_42") (pintype "passive"))
    )
    (net (code "149") (name "Net-(U2-VREF1)") (class "Default")
      (node (ref "C34") (pin "2") (pinfunction "2_2") (pintype "passive"))
      (node (ref "U2") (pin "35") (pinfunction "VREF1_35") (pintype "passive"))
    )
    (net (code "150") (name "Net-(U2-VREF2)") (class "Default")
      (node (ref "C32") (pin "2") (pinfunction "2_2") (pintype "passive"))
      (node (ref "R94") (pin "1") (pinfunction "1_1") (pintype "passive"))
      (node (ref "U2") (pin "34") (pinfunction "VREF2_34") (pintype "passive"))
    )
    (net (code "151") (name "Net-(U2-WDT)") (class "Default")
      (node (ref "J1") (pin "1") (pinfunction "1_1") (pintype "passive"))
      (node (ref "U2") (pin "39") (pinfunction "WDT_39") (pintype "passive"))
    )
    (net (code "152") (name "Net-(U3-C0)") (class "Default")
      (node (ref "R75") (pin "2") (pinfunction "2_2") (pintype "passive"))
      (node (ref "U3") (pin "26") (pinfunction "C0_26") (pintype "passive"))
    )
    (net (code "153") (name "Net-(U3-C1)") (class "Default")
      (node (ref "C24") (pin "1") (pinfunction "1_1") (pintype "passive"))
      (node (ref "C25") (pin "2") (pinfunction "2_2") (pintype "passive"))
      (node (ref "R49") (pin "2") (pinfunction "2_2") (pintype "passive"))
      (node (ref "U3") (pin "24") (pinfunction "C1_24") (pintype "passive"))
    )
    (net (code "154") (name "Net-(U3-C2)") (class "Default")
      (node (ref "C23") (pin "1") (pinfunction "1_1") (pintype "passive"))
      (node (ref "C24") (pin "2") (pinfunction "2_2") (pintype "passive"))
      (node (ref "R48") (pin "2") (pinfunction "2_2") (pintype "passive"))
      (node (ref "U3") (pin "22") (pinfunction "C2_22") (pintype "passive"))
    )
    (net (code "155") (name "Net-(U3-C3)") (class "Default")
      (node (ref "C22") (pin "1") (pinfunction "1_1") (pintype "passive"))
      (node (ref "C23") (pin "2") (pinfunction "2_2") (pintype "passive"))
      (node (ref "R47") (pin "2") (pinfunction "2_2") (pintype "passive"))
      (node (ref "U3") (pin "20") (pinfunction "C3_20") (pintype "passive"))
    )
    (net (code "156") (name "Net-(U3-C4)") (class "Default")
      (node (ref "C21") (pin "1") (pinfunction "1_1") (pintype "passive"))
      (node (ref "C22") (pin "2") (pinfunction "2_2") (pintype "passive"))
      (node (ref "R46") (pin "2") (pinfunction "2_2") (pintype "passive"))
      (node (ref "U3") (pin "18") (pinfunction "C4_18") (pintype "passive"))
    )
    (net (code "157") (name "Net-(U3-C5)") (class "Default")
      (node (ref "C20") (pin "1") (pinfunction "1_1") (pintype "passive"))
      (node (ref "C21") (pin "2") (pinfunction "2_2") (pintype "passive"))
      (node (ref "R45") (pin "2") (pinfunction "2_2") (pintype "passive"))
      (node (ref "U3") (pin "16") (pinfunction "C5_16") (pintype "passive"))
    )
    (net (code "158") (name "Net-(U3-C6)") (class "Default")
      (node (ref "C19") (pin "1") (pinfunction "1_1") (pintype "passive"))
      (node (ref "C20") (pin "2") (pinfunction "2_2") (pintype "passive"))
      (node (ref "R44") (pin "2") (pinfunction "2_2") (pintype "passive"))
      (node (ref "U3") (pin "14") (pinfunction "C6_14") (pintype "passive"))
    )
    (net (code "159") (name "Net-(U3-C7)") (class "Default")
      (node (ref "C18") (pin "1") (pinfunction "1_1") (pintype "passive"))
      (node (ref "C19") (pin "2") (pinfunction "2_2") (pintype "passive"))
      (node (ref "R43") (pin "2") (pinfunction "2_2") (pintype "passive"))
      (node (ref "U3") (pin "12") (pinfunction "C7_12") (pintype "passive"))
    )
    (net (code "160") (name "Net-(U3-C8)") (class "Default")
      (node (ref "C17") (pin "1") (pinfunction "1_1") (pintype "passive"))
      (node (ref "C18") (pin "2") (pinfunction "2_2") (pintype "passive"))
      (node (ref "R42") (pin "2") (pinfunction "2_2") (pintype "passive"))
      (node (ref "U3") (pin "10") (pinfunction "C8_10") (pintype "passive"))
    )
    (net (code "161") (name "Net-(U3-C9)") (class "Default")
      (node (ref "C16") (pin "1") (pinfunction "1_1") (pintype "passive"))
      (node (ref "C17") (pin "2") (pinfunction "2_2") (pintype "passive"))
      (node (ref "R41") (pin "2") (pinfunction "2_2") (pintype "passive"))
      (node (ref "U3") (pin "8") (pinfunction "C9_8") (pintype "passive"))
    )
    (net (code "162") (name "Net-(U3-C10)") (class "Default")
      (node (ref "C15") (pin "1") (pinfunction "1_1") (pintype "passive"))
      (node (ref "C16") (pin "2") (pinfunction "2_2") (pintype "passive"))
      (node (ref "R40") (pin "2") (pinfunction "2_2") (pintype "passive"))
      (node (ref "U3") (pin "6") (pinfunction "C10_6") (pintype "passive"))
    )
    (net (code "163") (name "Net-(U3-C11)") (class "Default")
      (node (ref "C14") (pin "1") (pinfunction "1_1") (pintype "passive"))
      (node (ref "C15") (pin "2") (pinfunction "2_2") (pintype "passive"))
      (node (ref "R39") (pin "2") (pinfunction "2_2") (pintype "passive"))
      (node (ref "U3") (pin "4") (pinfunction "C11_4") (pintype "passive"))
    )
    (net (code "164") (name "Net-(U3-C12)") (class "Default")
      (node (ref "C14") (pin "2") (pinfunction "2_2") (pintype "passive"))
      (node (ref "R38") (pin "2") (pinfunction "2_2") (pintype "passive"))
      (node (ref "U3") (pin "2") (pinfunction "C12_2") (pintype "passive"))
    )
    (net (code "165") (name "Net-(U3-DTEN)") (class "Default")
      (node (ref "J4") (pin "1") (pinfunction "1_1") (pintype "passive"))
      (node (ref "U3") (pin "36") (pinfunction "DTEN_36") (pintype "passive"))
    )
    (net (code "166") (name "Net-(U3-GPI03)") (class "Default")
      (node (ref "C39") (pin "2") (pinfunction "2_2") (pintype "passive"))
      (node (ref "J6") (pin "1") (pinfunction "1_1") (pintype "passive"))
      (node (ref "R95") (pin "2") (pinfunction "2_2") (pintype "passive"))
      (node (ref "U3") (pin "29") (pinfunction "GPI03_29") (pintype "passive"))
    )
    (net (code "167") (name "Net-(U3-IBIAS)") (class "Default")
      (node (ref "R84") (pin "2") (pinfunction "2_2") (pintype "passive"))
      (node (ref "U3") (pin "45") (pinfunction "IBIAS_45") (pintype "passive"))
    )
    (net (code "168") (name "Net-(U3-ICMP)") (class "Default")
      (node (ref "R84") (pin "1") (pinfunction "1_1") (pintype "passive"))
      (node (ref "R92") (pin "2") (pinfunction "2_2") (pintype "passive"))
      (node (ref "U3") (pin "46") (pinfunction "ICMP_46") (pintype "passive"))
    )
    (net (code "169") (name "Net-(U3-IMB)") (class "Default")
      (node (ref "C40") (pin "1") (pinfunction "1_1") (pintype "passive"))
      (node (ref "R98") (pin "2") (pinfunction "2_2") (pintype "passive"))
      (node (ref "U3") (pin "47") (pinfunction "IMB_47") (pintype "passive"))
    )
    (net (code "170") (name "Net-(U3-IPB)") (class "Default")
      (node (ref "C42") (pin "1") (pinfunction "1_1") (pintype "passive"))
      (node (ref "R98") (pin "1") (pinfunction "1_1") (pintype "passive"))
      (node (ref "U3") (pin "48") (pinfunction "IPB_48") (pintype "passive"))
    )
    (net (code "171") (name "Net-(U3-S1)") (class "Default")
      (node (ref "R74") (pin "2") (pinfunction "2_2") (pintype "passive"))
      (node (ref "U3") (pin "25") (pinfunction "S1_25") (pintype "passive"))
    )
    (net (code "172") (name "Net-(U3-S2)") (class "Default")
      (node (ref "R73") (pin "2") (pinfunction "2_2") (pintype "passive"))
      (node (ref "U3") (pin "23") (pinfunction "S2_23") (pintype "passive"))
    )
    (net (code "173") (name "Net-(U3-S3)") (class "Default")
      (node (ref "R72") (pin "2") (pinfunction "2_2") (pintype "passive"))
      (node (ref "U3") (pin "21") (pinfunction "S3_21") (pintype "passive"))
    )
    (net (code "174") (name "Net-(U3-S4)") (class "Default")
      (node (ref "R71") (pin "2") (pinfunction "2_2") (pintype "passive"))
      (node (ref "U3") (pin "19") (pinfunction "S4_19") (pintype "passive"))
    )
    (net (code "175") (name "Net-(U3-S5)") (class "Default")
      (node (ref "R70") (pin "2") (pinfunction "2_2") (pintype "passive"))
      (node (ref "U3") (pin "17") (pinfunction "S5_17") (pintype "passive"))
    )
    (net (code "176") (name "Net-(U3-S6)") (class "Default")
      (node (ref "R69") (pin "2") (pinfunction "2_2") (pintype "passive"))
      (node (ref "U3") (pin "15") (pinfunction "S6_15") (pintype "passive"))
    )
    (net (code "177") (name "Net-(U3-S7)") (class "Default")
      (node (ref "R68") (pin "2") (pinfunction "2_2") (pintype "passive"))
      (node (ref "U3") (pin "13") (pinfunction "S7_13") (pintype "passive"))
    )
    (net (code "178") (name "Net-(U3-S8)") (class "Default")
      (node (ref "R67") (pin "2") (pinfunction "2_2") (pintype "passive"))
      (node (ref "U3") (pin "11") (pinfunction "S8_11") (pintype "passive"))
    )
    (net (code "179") (name "Net-(U3-S9)") (class "Default")
      (node (ref "R66") (pin "2") (pinfunction "2_2") (pintype "passive"))
      (node (ref "U3") (pin "9") (pinfunction "S9_9") (pintype "passive"))
    )
    (net (code "180") (name "Net-(U3-S10)") (class "Default")
      (node (ref "R65") (pin "2") (pinfunction "2_2") (pintype "passive"))
      (node (ref "U3") (pin "7") (pinfunction "S10_7") (pintype "passive"))
    )
    (net (code "181") (name "Net-(U3-S11)") (class "Default")
      (node (ref "R64") (pin "2") (pinfunction "2_2") (pintype "passive"))
      (node (ref "U3") (pin "5") (pinfunction "S11_5") (pintype "passive"))
    )
    (net (code "182") (name "Net-(U3-S12)") (class "Default")
      (node (ref "R63") (pin "2") (pinfunction "2_2") (pintype "passive"))
      (node (ref "U3") (pin "3") (pinfunction "S12_3") (pintype "passive"))
    )
    (net (code "183") (name "Net-(U3-VREF1)") (class "Default")
      (node (ref "C35") (pin "2") (pinfunction "2_2") (pintype "passive"))
      (node (ref "U3") (pin "35") (pinfunction "VREF1_35") (pintype "passive"))
    )
    (net (code "184") (name "Net-(U3-VREF2)") (class "Default")
      (node (ref "C33") (pin "2") (pinfunction "2_2") (pintype "passive"))
      (node (ref "R95") (pin "1") (pinfunction "1_1") (pintype "passive"))
      (node (ref "U3") (pin "34") (pinfunction "VREF2_34") (pintype "passive"))
    )
    (net (code "185") (name "Net-(U3-WDT)") (class "Default")
      (node (ref "J3") (pin "1") (pinfunction "1_1") (pintype "passive"))
      (node (ref "U3") (pin "39") (pinfunction "WDT_39") (pintype "passive"))
    )
    (net (code "186") (name "Net-(U5-BAT)") (class "Default")
      (node (ref "C49") (pin "1") (pinfunction "1_1") (pintype "passive"))
      (node (ref "R108") (pin "1") (pinfunction "1_1") (pintype "passive"))
      (node (ref "R109") (pin "2") (pinfunction "2_2") (pintype "passive"))
      (node (ref "U5") (pin "4") (pinfunction "BAT_4") (pintype "passive"))
    )
    (net (code "187") (name "Net-(U5-CE)") (class "Default")
      (node (ref "C41") (pin "2") (pinfunction "2_2") (pintype "passive"))
      (node (ref "F2") (pin "1") (pinfunction "1_1") (pintype "passive"))
      (node (ref "U5") (pin "5") (pinfunction "CE_5") (pintype "passive"))
      (node (ref "U5") (pin "6") (pinfunction "REGIN_6") (pintype "passive"))
    )
    (net (code "188") (name "Net-(U5-P3{slash}SDA)") (class "Default")
      (node (ref "R79") (pin "1") (pinfunction "1_1") (pintype "passive"))
      (node (ref "R88") (pin "1") (pinfunction "1_1") (pintype "passive"))
      (node (ref "U5") (pin "14") (pinfunction "P3/SDA_14") (pintype "passive"))
    )
    (net (code "189") (name "Net-(U5-P4{slash}SCL)") (class "Default")
      (node (ref "R80") (pin "1") (pinfunction "1_1") (pintype "passive"))
      (node (ref "R81") (pin "1") (pinfunction "1_1") (pintype "passive"))
      (node (ref "U5") (pin "13") (pinfunction "P4/SCL_13") (pintype "passive"))
    )
    (net (code "190") (name "Net-(U5-P5{slash}HDQ)") (class "Default")
      (node (ref "J7") (pin "1") (pinfunction "1_1") (pintype "passive"))
      (node (ref "U5") (pin "12") (pinfunction "P5/HDQ_12") (pintype "passive"))
    )
    (net (code "191") (name "Net-(U5-P6{slash}TS)") (class "Default")
      (node (ref "J8") (pin "2") (pinfunction "2_2") (pintype "passive"))
      (node (ref "U5") (pin "11") (pinfunction "P6/TS_11") (pintype "passive"))
    )
    (net (code "192") (name "Net-(U5-SRN)") (class "Default")
      (node (ref "C44") (pin "2") (pinfunction "2_2") (pintype "passive"))
      (node (ref "C45") (pin "2") (pinfunction "2_2") (pintype "passive"))
      (node (ref "R103") (pin "2") (pinfunction "2_2") (pintype "passive"))
      (node (ref "U5") (pin "10") (pinfunction "SRN_10") (pintype "passive"))
    )
    (net (code "193") (name "Net-(U5-SRP)") (class "Default")
      (node (ref "C45") (pin "1") (pinfunction "1_1") (pintype "passive"))
      (node (ref "C46") (pin "2") (pinfunction "2_2") (pintype "passive"))
      (node (ref "R104") (pin "2") (pinfunction "2_2") (pintype "passive"))
      (node (ref "U5") (pin "9") (pinfunction "SRP_9") (pintype "passive"))
    )
    (net (code "194") (name "Net-(U5-VEN)") (class "Default")
      (node (ref "R102") (pin "2") (pinfunction "2_2") (pintype "passive"))
      (node (ref "U5") (pin "2") (pinfunction "VEN_2") (pintype "passive"))
    )
    (net (code "195") (name "Net-(U8-NRST)") (class "Default")
      (node (ref "C54") (pin "2") (pinfunction "2_2") (pintype "passive"))
      (node (ref "R111") (pin "2") (pinfunction "2_2") (pintype "passive"))
      (node (ref "U8") (pin "7") (pinfunction "NRST_7") (pintype "passive"))
    )
    (net (code "196") (name "Net-(U8-VDD_A)") (class "Default")
      (node (ref "C55") (pin "2") (pinfunction "2_2") (pintype "passive"))
      (node (ref "L2") (pin "2") (pinfunction "2_2") (pintype "passive"))
      (node (ref "U8") (pin "9") (pinfunction "VDD_A_9") (pintype "passive"))
    )
    (net (code "197") (name "Vb+") (class "Default")
      (node (ref "D8") (pin "2") (pinfunction "-_2") (pintype "passive"))
      (node (ref "F1") (pin "1") (pinfunction "1_1") (pintype "passive"))
      (node (ref "Q1") (pin "2") (pinfunction "SOURCE_2") (pintype "passive"))
      (node (ref "Q28") (pin "2") (pinfunction "SOURCE_2") (pintype "passive"))
      (node (ref "R105") (pin "2") (pinfunction "2_2") (pintype "passive"))
      (node (ref "R26") (pin "1") (pinfunction "1_1") (pintype "passive"))
      (node (ref "U2") (pin "1") (pinfunction "V+_1") (pintype "passive"))
    )
    (net (code "198") (name "Vb+_fuse") (class "Default")
      (node (ref "C1") (pin "2") (pinfunction "2_2") (pintype "passive"))
      (node (ref "F1") (pin "2") (pinfunction "2_2") (pintype "passive"))
      (node (ref "R99") (pin "1") (pinfunction "1_1") (pintype "passive"))
      (node (ref "U1") (pin "2") (pinfunction "VIN_2") (pintype "power_in"))
    )
    (net (code "199") (name "Vreg") (class "Default")
      (node (ref "C43") (pin "2") (pinfunction "2_2") (pintype "passive"))
      (node (ref "J8") (pin "1") (pinfunction "1_1") (pintype "passive"))
      (node (ref "U5") (pin "7") (pinfunction "REG25_7") (pintype "passive"))
    )
    (net (code "200") (name "unconnected-(Q25-DRAIN-Pad3)") (class "Default")
      (node (ref "Q25") (pin "3") (pinfunction "DRAIN_3") (pintype "passive"))
    )
    (net (code "201") (name "unconnected-(Q26-DRAIN-Pad3)") (class "Default")
      (node (ref "Q26") (pin "3") (pinfunction "DRAIN_3") (pintype "passive"))
    )
    (net (code "202") (name "unconnected-(U1-PG-Pad6)") (class "Default")
      (node (ref "U1") (pin "6") (pinfunction "PG_6") (pintype "open_collector"))
    )
    (net (code "203") (name "unconnected-(U2-DRIVE-Pad38)") (class "Default")
      (node (ref "U2") (pin "38") (pinfunction "DRIVE_38") (pintype "passive"))
    )
    (net (code "204") (name "unconnected-(U2-GPI01-Pad27)") (class "Default")
      (node (ref "U2") (pin "27") (pinfunction "GPI01_27") (pintype "passive"))
    )
    (net (code "205") (name "unconnected-(U2-GPI02-Pad28)") (class "Default")
      (node (ref "U2") (pin "28") (pinfunction "GPI02_28") (pintype "passive"))
    )
    (net (code "206") (name "unconnected-(U2-GPI04-Pad32)") (class "Default")
      (node (ref "U2") (pin "32") (pinfunction "GPI04_32") (pintype "passive"))
    )
    (net (code "207") (name "unconnected-(U2-GPI05-Pad33)") (class "Default")
      (node (ref "U2") (pin "33") (pinfunction "GPI05_33") (pintype "passive"))
    )
    (net (code "208") (name "unconnected-(U2-SDI(NC)-Pad43)") (class "Default")
      (node (ref "U2") (pin "43") (pinfunction "SDI(NC)_43") (pintype "passive"))
    )
    (net (code "209") (name "unconnected-(U2-SDO(NC)-Pad44)") (class "Default")
      (node (ref "U2") (pin "44") (pinfunction "SDO(NC)_44") (pintype "passive"))
    )
    (net (code "210") (name "unconnected-(U3-DRIVE-Pad38)") (class "Default")
      (node (ref "U3") (pin "38") (pinfunction "DRIVE_38") (pintype "passive"))
    )
    (net (code "211") (name "unconnected-(U3-GPI01-Pad27)") (class "Default")
      (node (ref "U3") (pin "27") (pinfunction "GPI01_27") (pintype "passive"))
    )
    (net (code "212") (name "unconnected-(U3-GPI02-Pad28)") (class "Default")
      (node (ref "U3") (pin "28") (pinfunction "GPI02_28") (pintype "passive"))
    )
    (net (code "213") (name "unconnected-(U8-PA0-Pad10)") (class "Default")
      (node (ref "U8") (pin "10") (pinfunction "PA0_10") (pintype "passive"))
    )
    (net (code "214") (name "unconnected-(U8-PA1-Pad11)") (class "Default")
      (node (ref "U8") (pin "11") (pinfunction "PA1_11") (pintype "passive"))
    )
    (net (code "215") (name "unconnected-(U8-PA2-Pad12)") (class "Default")
      (node (ref "U8") (pin "12") (pinfunction "PA2_12") (pintype "passive"))
    )
    (net (code "216") (name "unconnected-(U8-PA8-Pad29)") (class "Default")
      (node (ref "U8") (pin "29") (pinfunction "PA8_29") (pintype "passive"))
    )
    (net (code "217") (name "unconnected-(U8-PA9-Pad30)") (class "Default")
      (node (ref "U8") (pin "30") (pinfunction "PA9_30") (pintype "passive"))
    )
    (net (code "218") (name "unconnected-(U8-PA10-Pad31)") (class "Default")
      (node (ref "U8") (pin "31") (pinfunction "PA10_31") (pintype "passive"))
    )
    (net (code "219") (name "unconnected-(U8-PB0-Pad18)") (class "Default")
      (node (ref "U8") (pin "18") (pinfunction "PB0_18") (pintype "passive"))
    )
    (net (code "220") (name "unconnected-(U8-PB1-Pad19)") (class "Default")
      (node (ref "U8") (pin "19") (pinfunction "PB1_19") (pintype "passive"))
    )
    (net (code "221") (name "unconnected-(U8-PB2-Pad20)") (class "Default")
      (node (ref "U8") (pin "20") (pinfunction "PB2_20") (pintype "passive"))
    )
    (net (code "222") (name "unconnected-(U8-PB6-Pad42)") (class "Default")
      (node (ref "U8") (pin "42") (pinfunction "PB6_42") (pintype "passive"))
    )
    (net (code "223") (name "unconnected-(U8-PB7-Pad43)") (class "Default")
      (node (ref "U8") (pin "43") (pinfunction "PB7_43") (pintype "passive"))
    )
    (net (code "224") (name "unconnected-(U8-PB8-Pad45)") (class "Default")
      (node (ref "U8") (pin "45") (pinfunction "PB8_45") (pintype "passive"))
    )
    (net (code "225") (name "unconnected-(U8-PB9-Pad46)") (class "Default")
      (node (ref "U8") (pin "46") (pinfunction "PB9_46") (pintype "passive"))
    )
    (net (code "226") (name "unconnected-(U8-PB14-Pad27)") (class "Default")
      (node (ref "U8") (pin "27") (pinfunction "PB14_27") (pintype "passive"))
    )
    (net (code "227") (name "unconnected-(U8-PB15-Pad28)") (class "Default")
      (node (ref "U8") (pin "28") (pinfunction "PB15_28") (pintype "passive"))
    )
    (net (code "228") (name "unconnected-(U8-PC13-Pad2)") (class "Default")
      (node (ref "U8") (pin "2") (pinfunction "PC13_2") (pintype "passive"))
    )
    (net (code "229") (name "unconnected-(U8-PC14-Pad3)") (class "Default")
      (node (ref "U8") (pin "3") (pinfunction "PC14_3") (pintype "passive"))
    )
    (net (code "230") (name "unconnected-(U8-PC15-Pad4)") (class "Default")
      (node (ref "U8") (pin "4") (pinfunction "PC15_4") (pintype "passive"))
    )
    (net (code "231") (name "unconnected-(U8-PD0-Pad5)") (class "Default")
      (node (ref "U8") (pin "5") (pinfunction "PD0_5") (pintype "passive"))
    )
    (net (code "232") (name "unconnected-(U8-PD1-Pad6)") (class "Default")
      (node (ref "U8") (pin "6") (pinfunction "PD1_6") (pintype "passive"))
    )
  )
)
